# RF-OUT-001.net
KiCad netlist of a schematic drawn in EAGLE
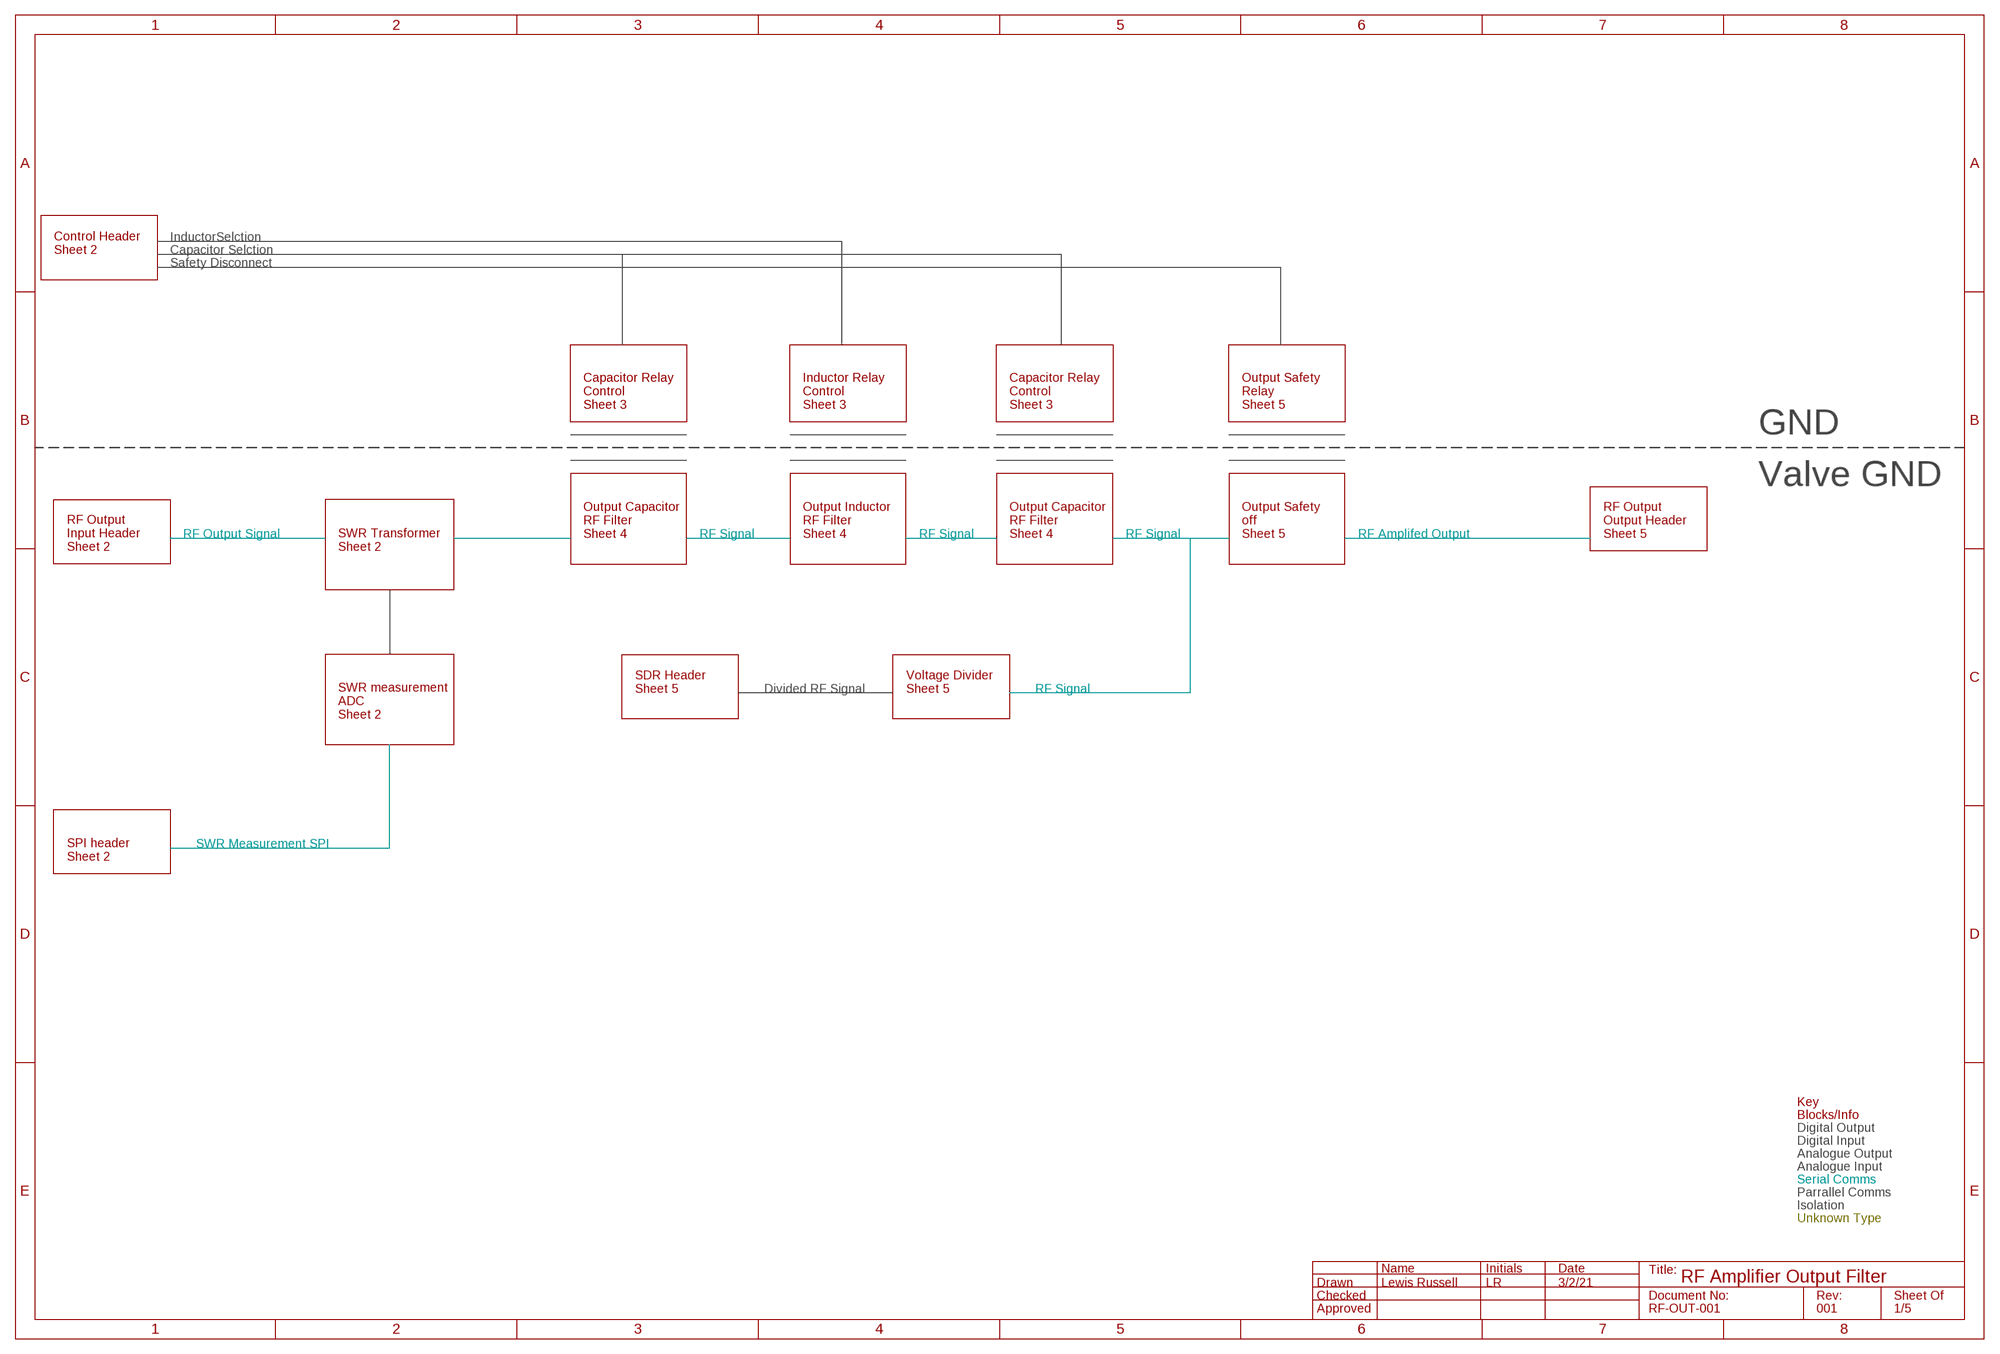
[diagram p0: schematic, sheet 1]
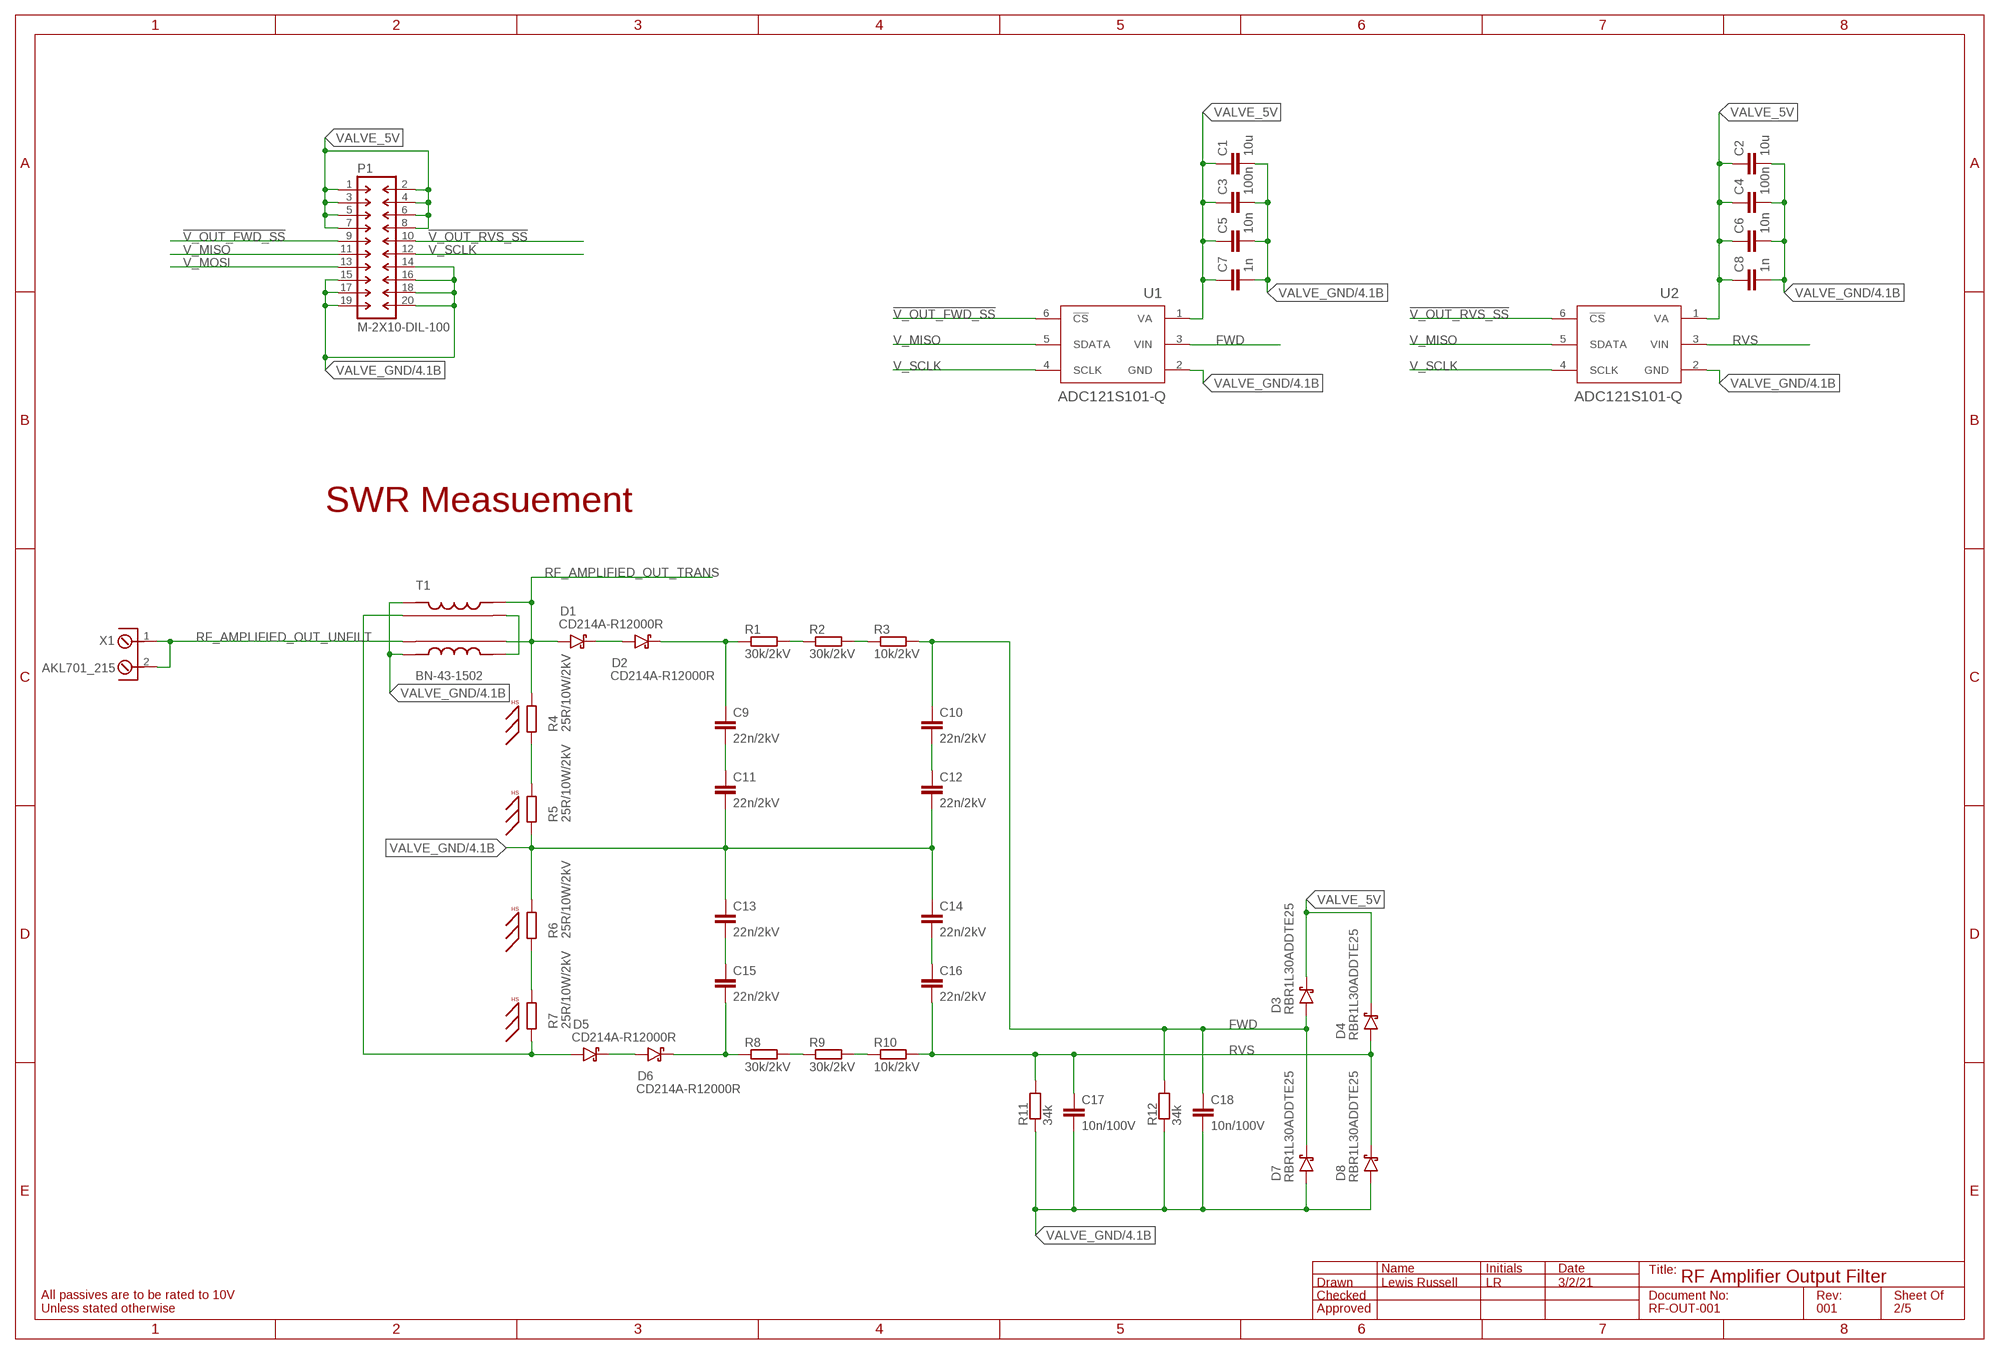
[diagram p1: schematic, sheet 2]
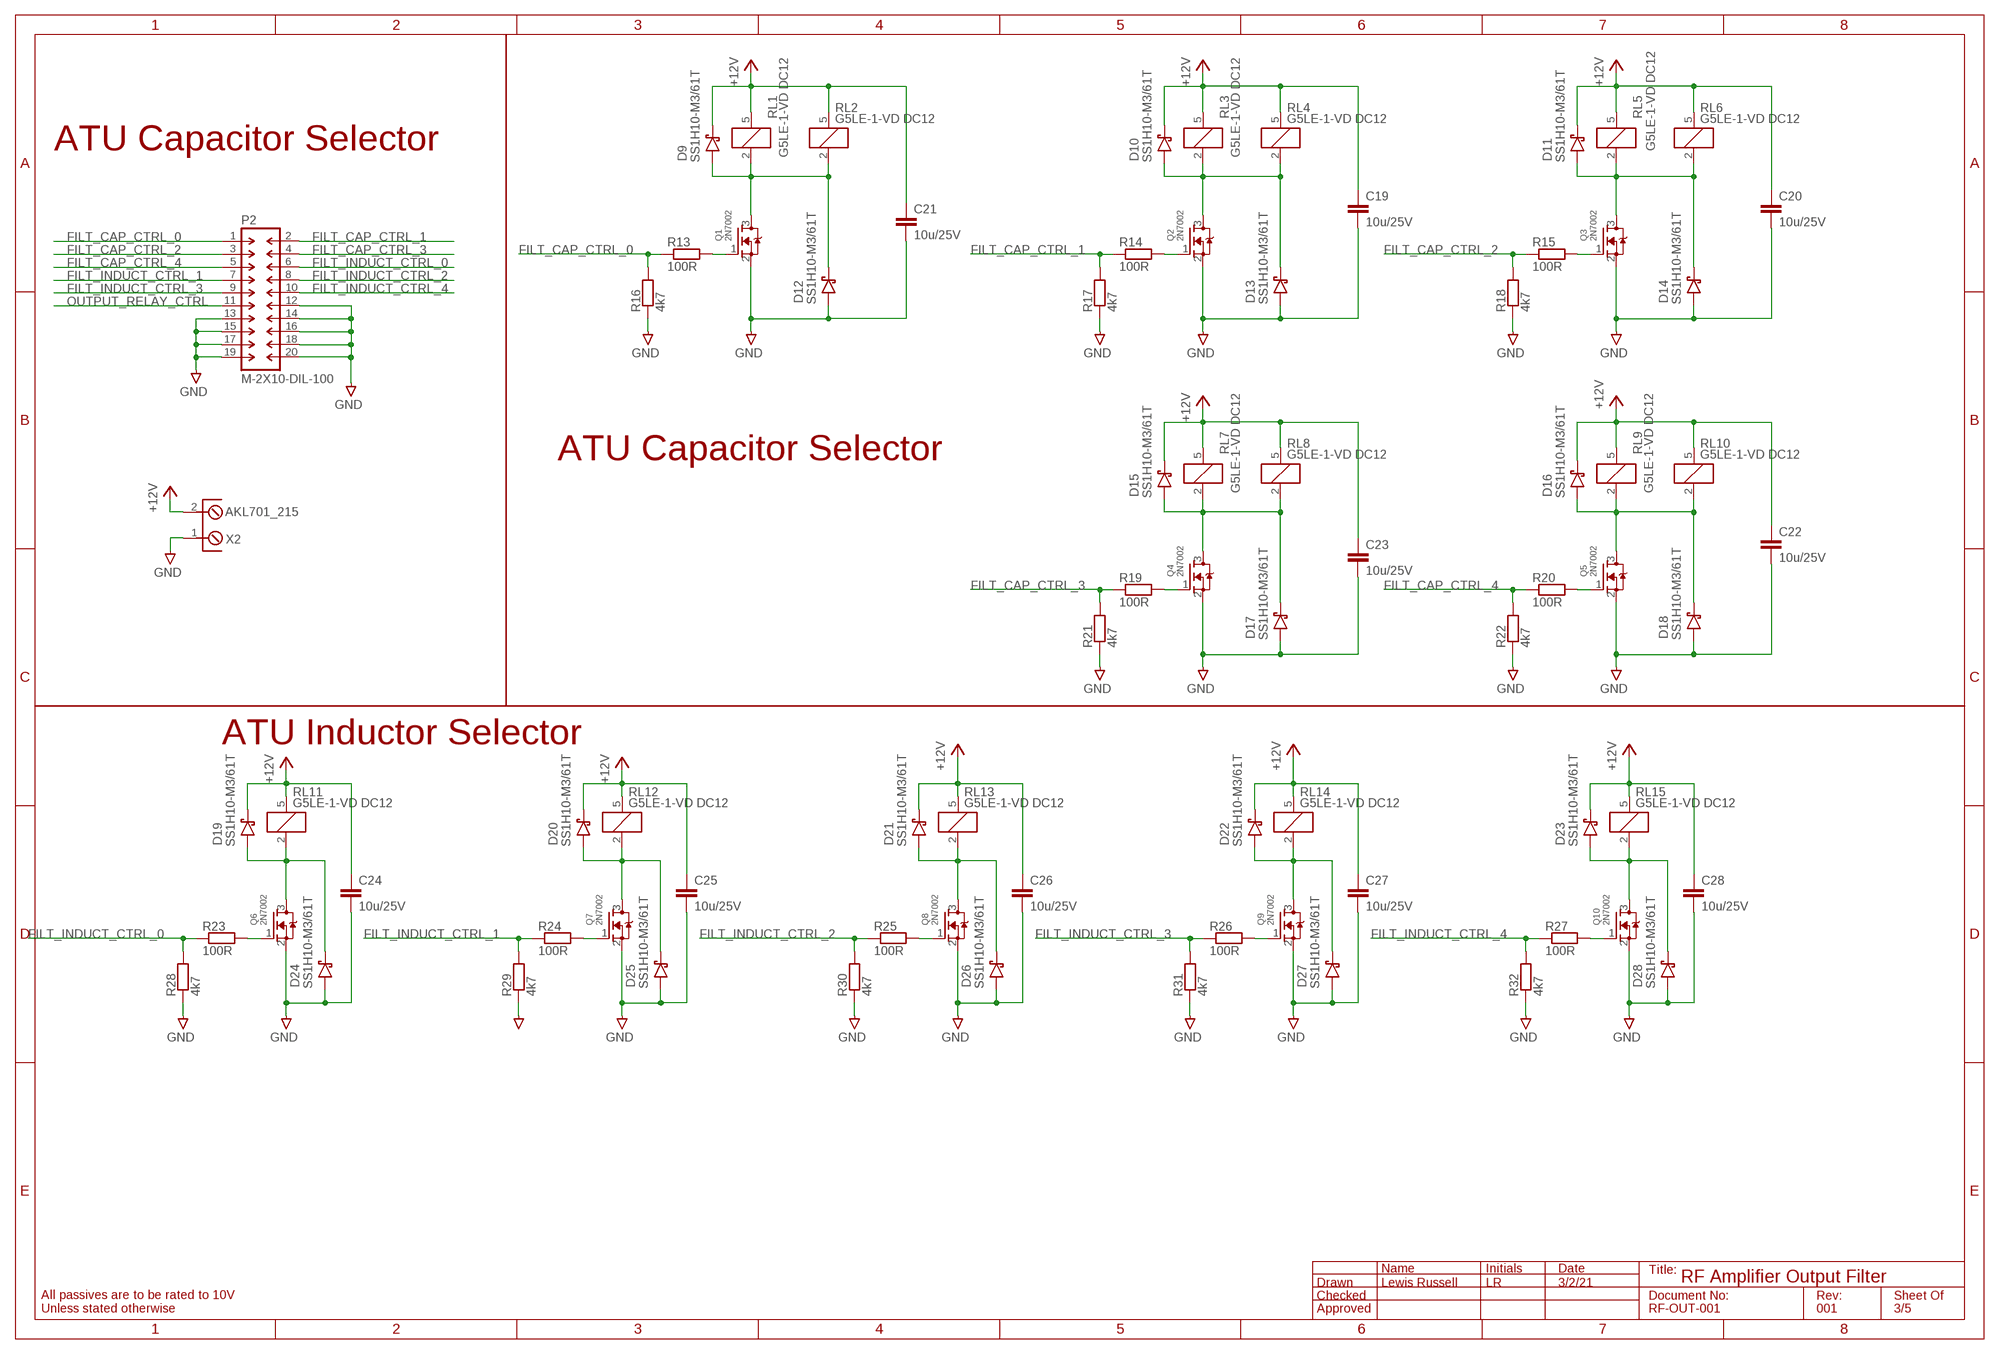
[diagram p2: schematic, sheet 3]
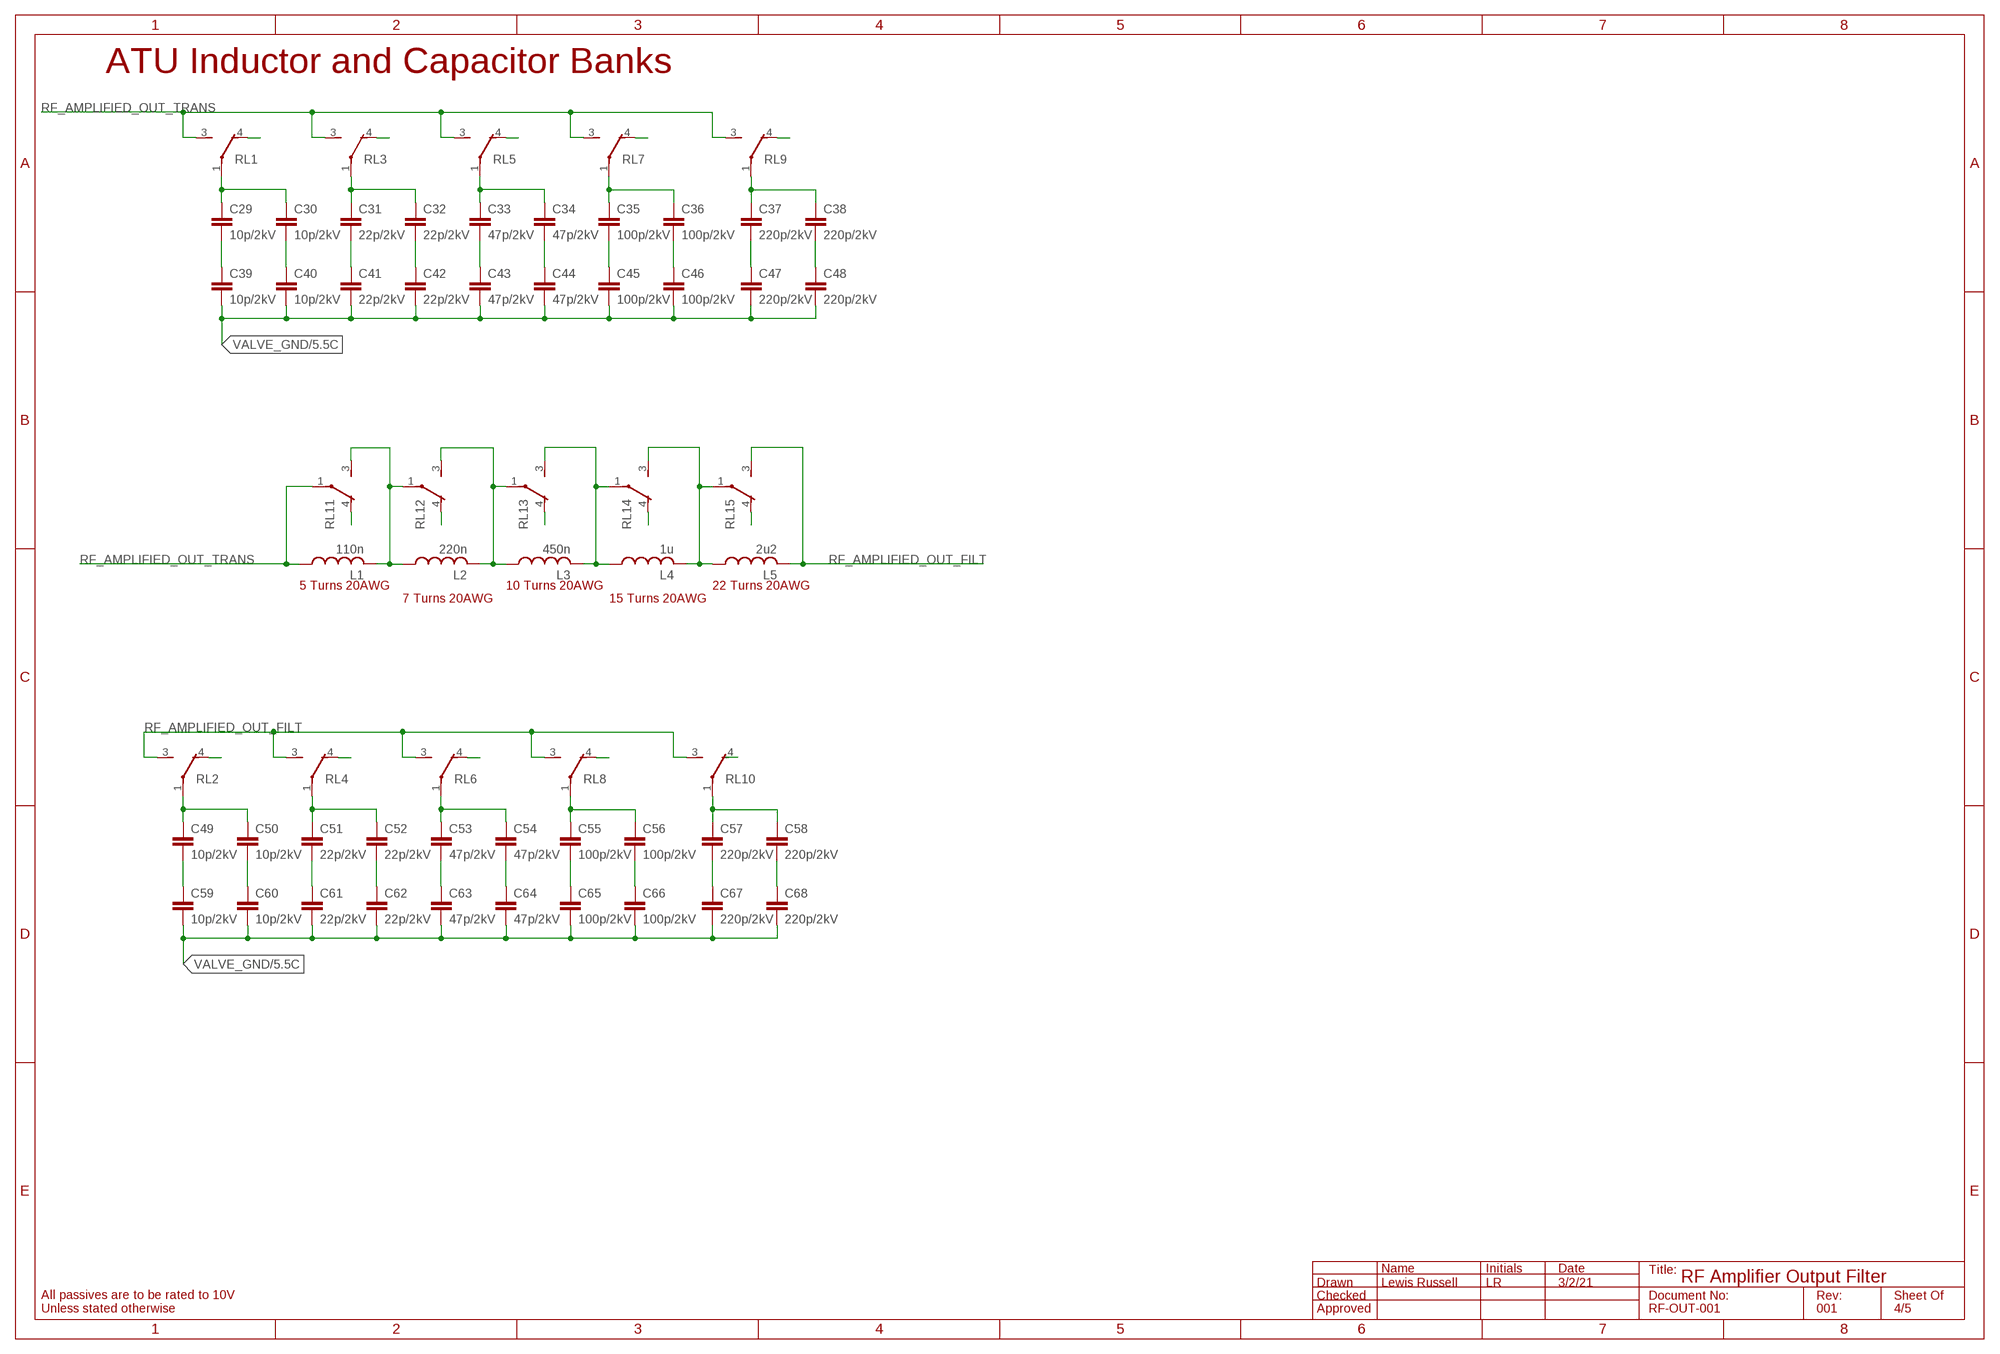
[diagram p3: schematic, sheet 4]
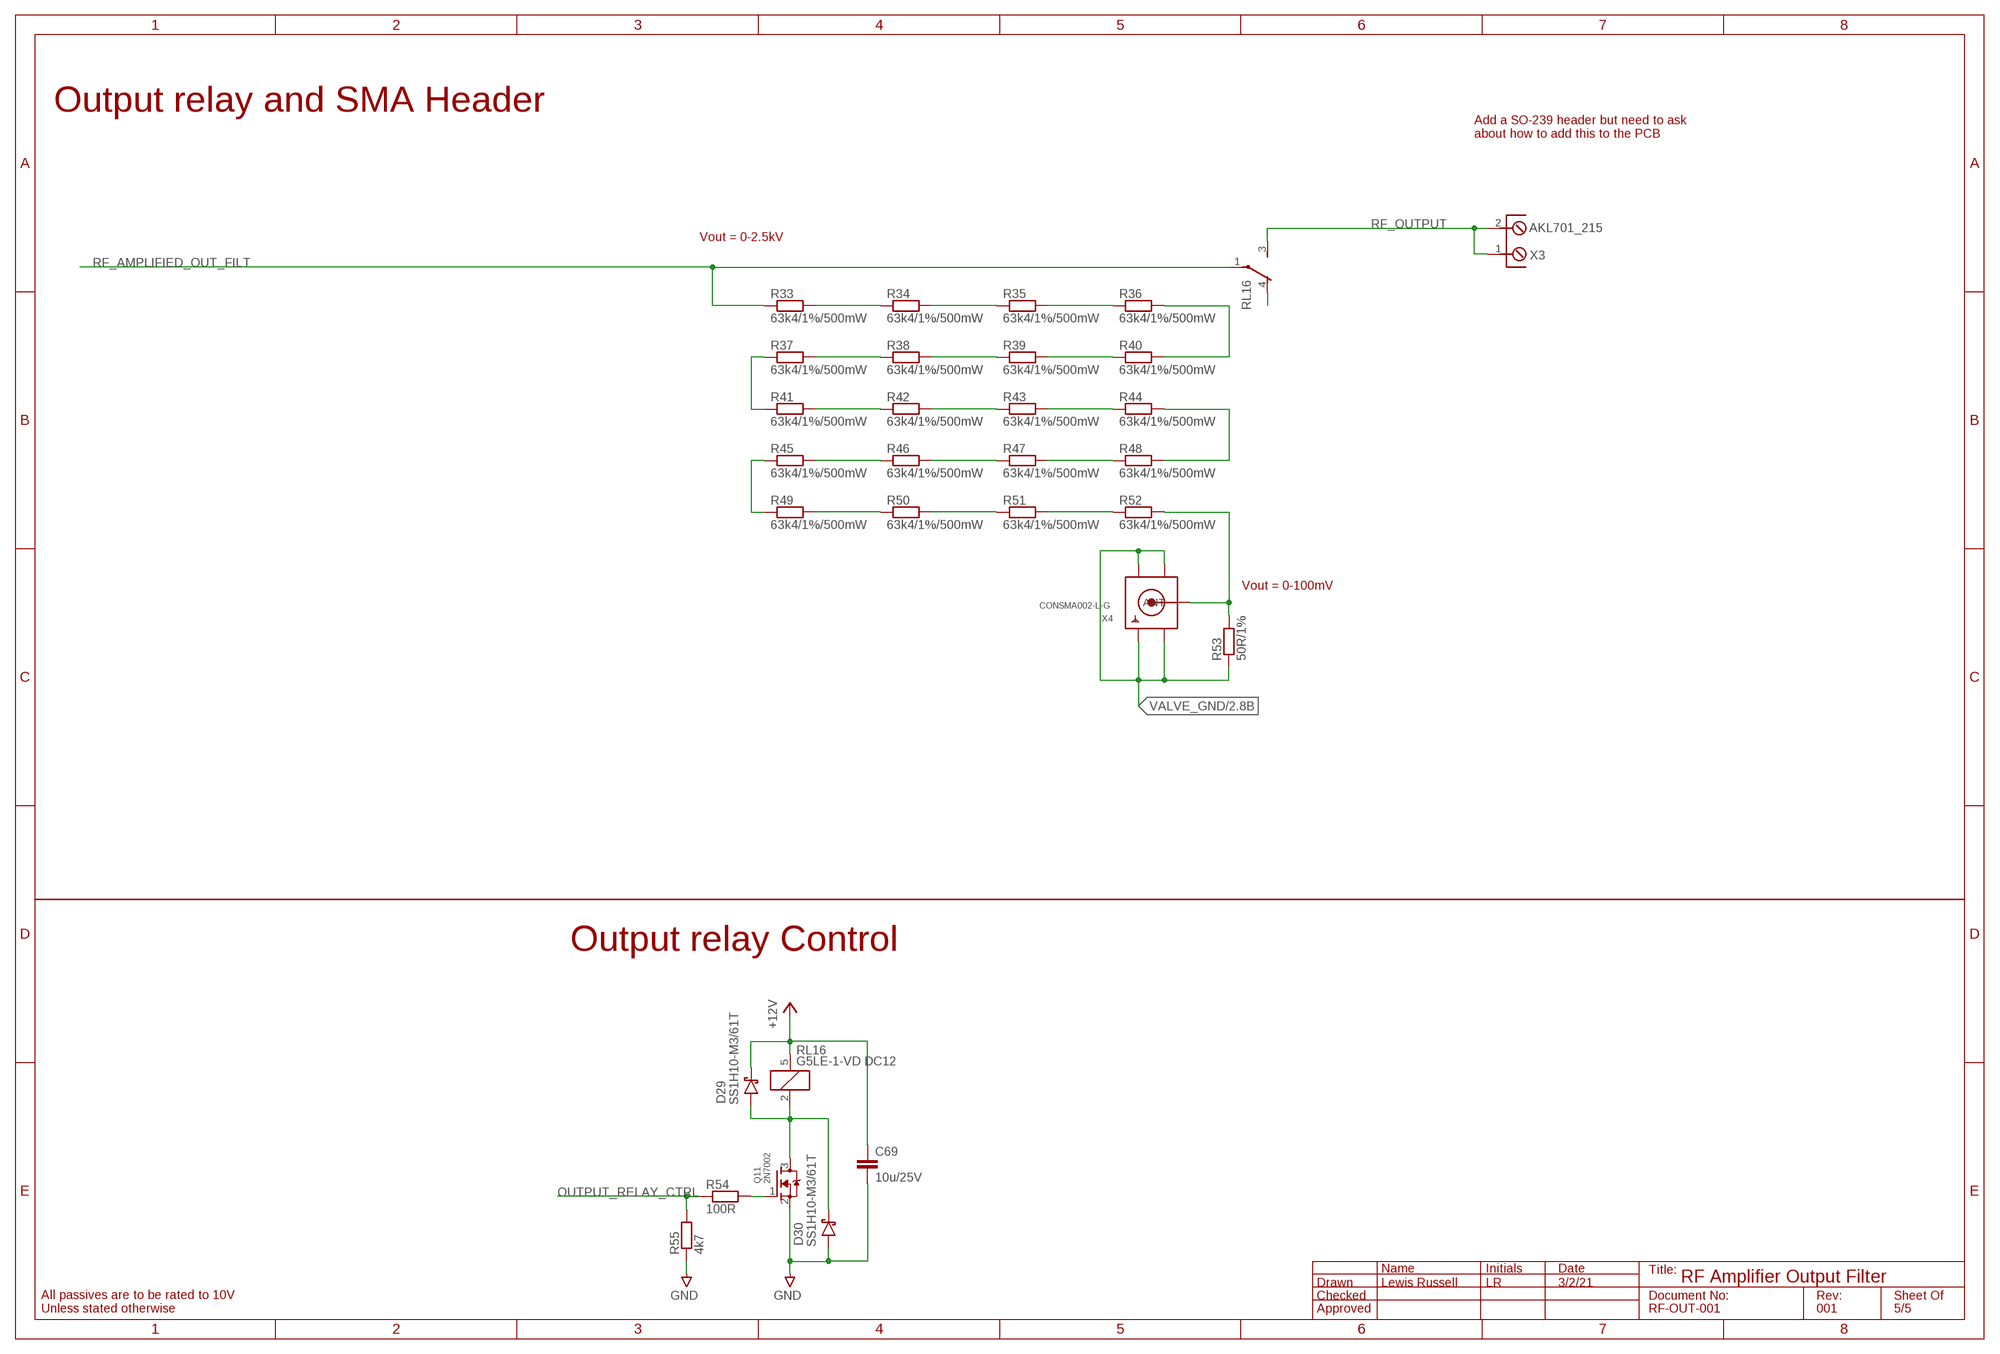
[diagram p4: schematic, sheet 5]

(export (version "E")
  (design (tool "Eeschema 10.0.6"))
  (components
    (comp (ref "C1")
      (value "10u")
      (footprint "eagle-import:C0805")
      (libsource (lib "eagle-import") (part "C-EUC0805"))
    )
    (comp (ref "C2")
      (value "10u")
      (footprint "eagle-import:C0805")
      (libsource (lib "eagle-import") (part "C-EUC0805"))
    )
    (comp (ref "C3")
      (value "100n")
      (footprint "eagle-import:C0603")
      (libsource (lib "eagle-import") (part "C-EUC0603"))
    )
    (comp (ref "C4")
      (value "100n")
      (footprint "eagle-import:C0603")
      (libsource (lib "eagle-import") (part "C-EUC0603"))
    )
    (comp (ref "C5")
      (value "10n")
      (footprint "eagle-import:C0603")
      (libsource (lib "eagle-import") (part "C-EUC0603"))
    )
    (comp (ref "C6")
      (value "10n")
      (footprint "eagle-import:C0603")
      (libsource (lib "eagle-import") (part "C-EUC0603"))
    )
    (comp (ref "C7")
      (value "1n")
      (footprint "eagle-import:C0603")
      (libsource (lib "eagle-import") (part "C-EUC0603"))
    )
    (comp (ref "C8")
      (value "1n")
      (footprint "eagle-import:C0603")
      (libsource (lib "eagle-import") (part "C-EUC0603"))
    )
    (comp (ref "C9")
      (value "22n/2kV")
      (footprint "eagle-import:C2220K")
      (libsource (lib "eagle-import") (part "C-EUC2220K"))
    )
    (comp (ref "C10")
      (value "22n/2kV")
      (footprint "eagle-import:C2220K")
      (libsource (lib "eagle-import") (part "C-EUC2220K"))
    )
    (comp (ref "C11")
      (value "22n/2kV")
      (footprint "eagle-import:C2220K")
      (libsource (lib "eagle-import") (part "C-EUC2220K"))
    )
    (comp (ref "C12")
      (value "22n/2kV")
      (footprint "eagle-import:C2220K")
      (libsource (lib "eagle-import") (part "C-EUC2220K"))
    )
    (comp (ref "C13")
      (value "22n/2kV")
      (footprint "eagle-import:C2220K")
      (libsource (lib "eagle-import") (part "C-EUC2220K"))
    )
    (comp (ref "C14")
      (value "22n/2kV")
      (footprint "eagle-import:C2220K")
      (libsource (lib "eagle-import") (part "C-EUC2220K"))
    )
    (comp (ref "C15")
      (value "22n/2kV")
      (footprint "eagle-import:C2220K")
      (libsource (lib "eagle-import") (part "C-EUC2220K"))
    )
    (comp (ref "C16")
      (value "22n/2kV")
      (footprint "eagle-import:C2220K")
      (libsource (lib "eagle-import") (part "C-EUC2220K"))
    )
    (comp (ref "C17")
      (value "10n/100V")
      (footprint "eagle-import:C0603")
      (libsource (lib "eagle-import") (part "C-EUC0603"))
    )
    (comp (ref "C18")
      (value "10n/100V")
      (footprint "eagle-import:C0603")
      (libsource (lib "eagle-import") (part "C-EUC0603"))
    )
    (comp (ref "D1")
      (value "CD214A-R12000R")
      (footprint "eagle-import:SMB_DO-214AA")
      (libsource (lib "eagle-import") (part "SCHOTTKY_DIODESMB"))
    )
    (comp (ref "D2")
      (value "CD214A-R12000R")
      (footprint "eagle-import:SMB_DO-214AA")
      (libsource (lib "eagle-import") (part "SCHOTTKY_DIODESMB"))
    )
    (comp (ref "D3")
      (value "RBR1L30ADDTE25")
      (footprint "eagle-import:SMA_DO-214AC")
      (libsource (lib "eagle-import") (part "SCHOTTKY_DIODESMA"))
    )
    (comp (ref "D4")
      (value "RBR1L30ADDTE25")
      (footprint "eagle-import:SMA_DO-214AC")
      (libsource (lib "eagle-import") (part "SCHOTTKY_DIODESMA"))
    )
    (comp (ref "D5")
      (value "CD214A-R12000R")
      (footprint "eagle-import:SMB_DO-214AA")
      (libsource (lib "eagle-import") (part "SCHOTTKY_DIODESMB"))
    )
    (comp (ref "D6")
      (value "CD214A-R12000R")
      (footprint "eagle-import:SMB_DO-214AA")
      (libsource (lib "eagle-import") (part "SCHOTTKY_DIODESMB"))
    )
    (comp (ref "D7")
      (value "RBR1L30ADDTE25")
      (footprint "eagle-import:SMA_DO-214AC")
      (libsource (lib "eagle-import") (part "SCHOTTKY_DIODESMA"))
    )
    (comp (ref "D8")
      (value "RBR1L30ADDTE25")
      (footprint "eagle-import:SMA_DO-214AC")
      (libsource (lib "eagle-import") (part "SCHOTTKY_DIODESMA"))
    )
    (comp (ref "P1")
      (value "M-2X10-DIL-100")
      (footprint "eagle-import:DIL-100-2X10")
      (libsource (lib "eagle-import") (part "M-2X10-DIL-100"))
    )
    (comp (ref "R1")
      (value "30k/2kV")
      (footprint "eagle-import:0309_10")
      (libsource (lib "eagle-import") (part "R-EU_0309/10"))
    )
    (comp (ref "R2")
      (value "30k/2kV")
      (footprint "eagle-import:0309_10")
      (libsource (lib "eagle-import") (part "R-EU_0309/10"))
    )
    (comp (ref "R3")
      (value "10k/2kV")
      (footprint "eagle-import:0309_10")
      (libsource (lib "eagle-import") (part "R-EU_0309/10"))
    )
    (comp (ref "R4")
      (value "25R/10W/2kV")
      (footprint "eagle-import:TO220ACS_WITH_WV-T220-101E")
      (libsource (lib "eagle-import") (part "R-EU_W_HS_TO-220-WV-T220-101E"))
    )
    (comp (ref "R5")
      (value "25R/10W/2kV")
      (footprint "eagle-import:TO220ACS_WITH_WV-T220-101E")
      (libsource (lib "eagle-import") (part "R-EU_W_HS_TO-220-WV-T220-101E"))
    )
    (comp (ref "R6")
      (value "25R/10W/2kV")
      (footprint "eagle-import:TO220ACS_WITH_WV-T220-101E")
      (libsource (lib "eagle-import") (part "R-EU_W_HS_TO-220-WV-T220-101E"))
    )
    (comp (ref "R7")
      (value "25R/10W/2kV")
      (footprint "eagle-import:TO220ACS_WITH_WV-T220-101E")
      (libsource (lib "eagle-import") (part "R-EU_W_HS_TO-220-WV-T220-101E"))
    )
    (comp (ref "R8")
      (value "30k/2kV")
      (footprint "eagle-import:0309_10")
      (libsource (lib "eagle-import") (part "R-EU_0309/10"))
    )
    (comp (ref "R9")
      (value "30k/2kV")
      (footprint "eagle-import:0309_10")
      (libsource (lib "eagle-import") (part "R-EU_0309/10"))
    )
    (comp (ref "R10")
      (value "10k/2kV")
      (footprint "eagle-import:0309_10")
      (libsource (lib "eagle-import") (part "R-EU_0309/10"))
    )
    (comp (ref "R11")
      (value "34k")
      (footprint "eagle-import:R0603")
      (libsource (lib "eagle-import") (part "R-EUR0603"))
    )
    (comp (ref "R12")
      (value "34k")
      (footprint "eagle-import:R0603")
      (libsource (lib "eagle-import") (part "R-EUR0603"))
    )
    (comp (ref "T1")
      (value "BN-43-1502")
      (footprint "eagle-import:BN-43-1502")
      (libsource (lib "eagle-import") (part "BN-43-1502"))
    )
    (comp (ref "U1")
      (value "ADC121S101-Q")
      (footprint "eagle-import:SOT23-6")
      (libsource (lib "eagle-import") (part "ADC121S101-Q"))
    )
    (comp (ref "U2")
      (value "ADC121S101-Q")
      (footprint "eagle-import:SOT23-6")
      (libsource (lib "eagle-import") (part "ADC121S101-Q"))
    )
    (comp (ref "X1")
      (value "AKL701_215")
      (footprint "eagle-import:AKL701_2_15")
      (libsource (lib "eagle-import") (part "AKL701_215"))
    )
    (comp (ref "C19")
      (value "10u/25V")
      (footprint "eagle-import:C0805")
      (libsource (lib "eagle-import") (part "C-EUC0805"))
    )
    (comp (ref "C20")
      (value "10u/25V")
      (footprint "eagle-import:C0805")
      (libsource (lib "eagle-import") (part "C-EUC0805"))
    )
    (comp (ref "C21")
      (value "10u/25V")
      (footprint "eagle-import:C0805")
      (libsource (lib "eagle-import") (part "C-EUC0805"))
    )
    (comp (ref "C22")
      (value "10u/25V")
      (footprint "eagle-import:C0805")
      (libsource (lib "eagle-import") (part "C-EUC0805"))
    )
    (comp (ref "C23")
      (value "10u/25V")
      (footprint "eagle-import:C0805")
      (libsource (lib "eagle-import") (part "C-EUC0805"))
    )
    (comp (ref "C24")
      (value "10u/25V")
      (footprint "eagle-import:C0805")
      (libsource (lib "eagle-import") (part "C-EUC0805"))
    )
    (comp (ref "C25")
      (value "10u/25V")
      (footprint "eagle-import:C0805")
      (libsource (lib "eagle-import") (part "C-EUC0805"))
    )
    (comp (ref "C26")
      (value "10u/25V")
      (footprint "eagle-import:C0805")
      (libsource (lib "eagle-import") (part "C-EUC0805"))
    )
    (comp (ref "C27")
      (value "10u/25V")
      (footprint "eagle-import:C0805")
      (libsource (lib "eagle-import") (part "C-EUC0805"))
    )
    (comp (ref "C28")
      (value "10u/25V")
      (footprint "eagle-import:C0805")
      (libsource (lib "eagle-import") (part "C-EUC0805"))
    )
    (comp (ref "D9")
      (value "SS1H10-M3/61T")
      (footprint "eagle-import:SMA_DO-214AC")
      (libsource (lib "eagle-import") (part "SCHOTTKY_DIODESMA"))
    )
    (comp (ref "D10")
      (value "SS1H10-M3/61T")
      (footprint "eagle-import:SMA_DO-214AC")
      (libsource (lib "eagle-import") (part "SCHOTTKY_DIODESMA"))
    )
    (comp (ref "D11")
      (value "SS1H10-M3/61T")
      (footprint "eagle-import:SMA_DO-214AC")
      (libsource (lib "eagle-import") (part "SCHOTTKY_DIODESMA"))
    )
    (comp (ref "D12")
      (value "SS1H10-M3/61T")
      (footprint "eagle-import:SMA_DO-214AC")
      (libsource (lib "eagle-import") (part "SCHOTTKY_DIODESMA"))
    )
    (comp (ref "D13")
      (value "SS1H10-M3/61T")
      (footprint "eagle-import:SMA_DO-214AC")
      (libsource (lib "eagle-import") (part "SCHOTTKY_DIODESMA"))
    )
    (comp (ref "D14")
      (value "SS1H10-M3/61T")
      (footprint "eagle-import:SMA_DO-214AC")
      (libsource (lib "eagle-import") (part "SCHOTTKY_DIODESMA"))
    )
    (comp (ref "D15")
      (value "SS1H10-M3/61T")
      (footprint "eagle-import:SMA_DO-214AC")
      (libsource (lib "eagle-import") (part "SCHOTTKY_DIODESMA"))
    )
    (comp (ref "D16")
      (value "SS1H10-M3/61T")
      (footprint "eagle-import:SMA_DO-214AC")
      (libsource (lib "eagle-import") (part "SCHOTTKY_DIODESMA"))
    )
    (comp (ref "D17")
      (value "SS1H10-M3/61T")
      (footprint "eagle-import:SMA_DO-214AC")
      (libsource (lib "eagle-import") (part "SCHOTTKY_DIODESMA"))
    )
    (comp (ref "D18")
      (value "SS1H10-M3/61T")
      (footprint "eagle-import:SMA_DO-214AC")
      (libsource (lib "eagle-import") (part "SCHOTTKY_DIODESMA"))
    )
    (comp (ref "D19")
      (value "SS1H10-M3/61T")
      (footprint "eagle-import:SMA_DO-214AC")
      (libsource (lib "eagle-import") (part "SCHOTTKY_DIODESMA"))
    )
    (comp (ref "D20")
      (value "SS1H10-M3/61T")
      (footprint "eagle-import:SMA_DO-214AC")
      (libsource (lib "eagle-import") (part "SCHOTTKY_DIODESMA"))
    )
    (comp (ref "D21")
      (value "SS1H10-M3/61T")
      (footprint "eagle-import:SMA_DO-214AC")
      (libsource (lib "eagle-import") (part "SCHOTTKY_DIODESMA"))
    )
    (comp (ref "D22")
      (value "SS1H10-M3/61T")
      (footprint "eagle-import:SMA_DO-214AC")
      (libsource (lib "eagle-import") (part "SCHOTTKY_DIODESMA"))
    )
    (comp (ref "D23")
      (value "SS1H10-M3/61T")
      (footprint "eagle-import:SMA_DO-214AC")
      (libsource (lib "eagle-import") (part "SCHOTTKY_DIODESMA"))
    )
    (comp (ref "D24")
      (value "SS1H10-M3/61T")
      (footprint "eagle-import:SMA_DO-214AC")
      (libsource (lib "eagle-import") (part "SCHOTTKY_DIODESMA"))
    )
    (comp (ref "D25")
      (value "SS1H10-M3/61T")
      (footprint "eagle-import:SMA_DO-214AC")
      (libsource (lib "eagle-import") (part "SCHOTTKY_DIODESMA"))
    )
    (comp (ref "D26")
      (value "SS1H10-M3/61T")
      (footprint "eagle-import:SMA_DO-214AC")
      (libsource (lib "eagle-import") (part "SCHOTTKY_DIODESMA"))
    )
    (comp (ref "D27")
      (value "SS1H10-M3/61T")
      (footprint "eagle-import:SMA_DO-214AC")
      (libsource (lib "eagle-import") (part "SCHOTTKY_DIODESMA"))
    )
    (comp (ref "D28")
      (value "SS1H10-M3/61T")
      (footprint "eagle-import:SMA_DO-214AC")
      (libsource (lib "eagle-import") (part "SCHOTTKY_DIODESMA"))
    )
    (comp (ref "P2")
      (value "M-2X10-DIL-100")
      (footprint "eagle-import:DIL-100-2X10")
      (libsource (lib "eagle-import") (part "M-2X10-DIL-100"))
    )
    (comp (ref "Q1")
      (value "2N7002")
      (footprint "eagle-import:SOT23")
      (libsource (lib "eagle-import") (part "MOSFET-NREFLOW"))
    )
    (comp (ref "Q2")
      (value "2N7002")
      (footprint "eagle-import:SOT23")
      (libsource (lib "eagle-import") (part "MOSFET-NREFLOW"))
    )
    (comp (ref "Q3")
      (value "2N7002")
      (footprint "eagle-import:SOT23")
      (libsource (lib "eagle-import") (part "MOSFET-NREFLOW"))
    )
    (comp (ref "Q4")
      (value "2N7002")
      (footprint "eagle-import:SOT23")
      (libsource (lib "eagle-import") (part "MOSFET-NREFLOW"))
    )
    (comp (ref "Q5")
      (value "2N7002")
      (footprint "eagle-import:SOT23")
      (libsource (lib "eagle-import") (part "MOSFET-NREFLOW"))
    )
    (comp (ref "Q6")
      (value "2N7002")
      (footprint "eagle-import:SOT23")
      (libsource (lib "eagle-import") (part "MOSFET-NREFLOW"))
    )
    (comp (ref "Q7")
      (value "2N7002")
      (footprint "eagle-import:SOT23")
      (libsource (lib "eagle-import") (part "MOSFET-NREFLOW"))
    )
    (comp (ref "Q8")
      (value "2N7002")
      (footprint "eagle-import:SOT23")
      (libsource (lib "eagle-import") (part "MOSFET-NREFLOW"))
    )
    (comp (ref "Q9")
      (value "2N7002")
      (footprint "eagle-import:SOT23")
      (libsource (lib "eagle-import") (part "MOSFET-NREFLOW"))
    )
    (comp (ref "Q10")
      (value "2N7002")
      (footprint "eagle-import:SOT23")
      (libsource (lib "eagle-import") (part "MOSFET-NREFLOW"))
    )
    (comp (ref "R13")
      (value "100R")
      (footprint "eagle-import:R0603")
      (libsource (lib "eagle-import") (part "R-EUR0603"))
    )
    (comp (ref "R14")
      (value "100R")
      (footprint "eagle-import:R0603")
      (libsource (lib "eagle-import") (part "R-EUR0603"))
    )
    (comp (ref "R15")
      (value "100R")
      (footprint "eagle-import:R0603")
      (libsource (lib "eagle-import") (part "R-EUR0603"))
    )
    (comp (ref "R16")
      (value "4k7")
      (footprint "eagle-import:R0603")
      (libsource (lib "eagle-import") (part "R-EUR0603"))
    )
    (comp (ref "R17")
      (value "4k7")
      (footprint "eagle-import:R0603")
      (libsource (lib "eagle-import") (part "R-EUR0603"))
    )
    (comp (ref "R18")
      (value "4k7")
      (footprint "eagle-import:R0603")
      (libsource (lib "eagle-import") (part "R-EUR0603"))
    )
    (comp (ref "R19")
      (value "100R")
      (footprint "eagle-import:R0603")
      (libsource (lib "eagle-import") (part "R-EUR0603"))
    )
    (comp (ref "R20")
      (value "100R")
      (footprint "eagle-import:R0603")
      (libsource (lib "eagle-import") (part "R-EUR0603"))
    )
    (comp (ref "R21")
      (value "4k7")
      (footprint "eagle-import:R0603")
      (libsource (lib "eagle-import") (part "R-EUR0603"))
    )
    (comp (ref "R22")
      (value "4k7")
      (footprint "eagle-import:R0603")
      (libsource (lib "eagle-import") (part "R-EUR0603"))
    )
    (comp (ref "R23")
      (value "100R")
      (footprint "eagle-import:R0603")
      (libsource (lib "eagle-import") (part "R-EUR0603"))
    )
    (comp (ref "R24")
      (value "100R")
      (footprint "eagle-import:R0603")
      (libsource (lib "eagle-import") (part "R-EUR0603"))
    )
    (comp (ref "R25")
      (value "100R")
      (footprint "eagle-import:R0603")
      (libsource (lib "eagle-import") (part "R-EUR0603"))
    )
    (comp (ref "R26")
      (value "100R")
      (footprint "eagle-import:R0603")
      (libsource (lib "eagle-import") (part "R-EUR0603"))
    )
    (comp (ref "R27")
      (value "100R")
      (footprint "eagle-import:R0603")
      (libsource (lib "eagle-import") (part "R-EUR0603"))
    )
    (comp (ref "R28")
      (value "4k7")
      (footprint "eagle-import:R0603")
      (libsource (lib "eagle-import") (part "R-EUR0603"))
    )
    (comp (ref "R29")
      (value "4k7")
      (footprint "eagle-import:R0603")
      (libsource (lib "eagle-import") (part "R-EUR0603"))
    )
    (comp (ref "R30")
      (value "4k7")
      (footprint "eagle-import:R0603")
      (libsource (lib "eagle-import") (part "R-EUR0603"))
    )
    (comp (ref "R31")
      (value "4k7")
      (footprint "eagle-import:R0603")
      (libsource (lib "eagle-import") (part "R-EUR0603"))
    )
    (comp (ref "R32")
      (value "4k7")
      (footprint "eagle-import:R0603")
      (libsource (lib "eagle-import") (part "R-EUR0603"))
    )
    (comp (ref "RL1")
      (value "G5LE-1-VD DC12")
      (footprint "eagle-import:SPDT")
      (libsource (lib "eagle-import") (part "G5LE-E"))
    )
    (comp (ref "RL2")
      (value "G5LE-1-VD DC12")
      (footprint "eagle-import:SPDT")
      (libsource (lib "eagle-import") (part "G5LE-E"))
    )
    (comp (ref "RL3")
      (value "G5LE-1-VD DC12")
      (footprint "eagle-import:SPDT")
      (libsource (lib "eagle-import") (part "G5LE-E"))
    )
    (comp (ref "RL4")
      (value "G5LE-1-VD DC12")
      (footprint "eagle-import:SPDT")
      (libsource (lib "eagle-import") (part "G5LE-E"))
    )
    (comp (ref "RL5")
      (value "G5LE-1-VD DC12")
      (footprint "eagle-import:SPDT")
      (libsource (lib "eagle-import") (part "G5LE-E"))
    )
    (comp (ref "RL6")
      (value "G5LE-1-VD DC12")
      (footprint "eagle-import:SPDT")
      (libsource (lib "eagle-import") (part "G5LE-E"))
    )
    (comp (ref "RL7")
      (value "G5LE-1-VD DC12")
      (footprint "eagle-import:SPDT")
      (libsource (lib "eagle-import") (part "G5LE-E"))
    )
    (comp (ref "RL8")
      (value "G5LE-1-VD DC12")
      (footprint "eagle-import:SPDT")
      (libsource (lib "eagle-import") (part "G5LE-E"))
    )
    (comp (ref "RL9")
      (value "G5LE-1-VD DC12")
      (footprint "eagle-import:SPDT")
      (libsource (lib "eagle-import") (part "G5LE-E"))
    )
    (comp (ref "RL10")
      (value "G5LE-1-VD DC12")
      (footprint "eagle-import:SPDT")
      (libsource (lib "eagle-import") (part "G5LE-E"))
    )
    (comp (ref "RL11")
      (value "G5LE-1-VD DC12")
      (footprint "eagle-import:SPDT")
      (libsource (lib "eagle-import") (part "G5LE-E"))
    )
    (comp (ref "RL12")
      (value "G5LE-1-VD DC12")
      (footprint "eagle-import:SPDT")
      (libsource (lib "eagle-import") (part "G5LE-E"))
    )
    (comp (ref "RL13")
      (value "G5LE-1-VD DC12")
      (footprint "eagle-import:SPDT")
      (libsource (lib "eagle-import") (part "G5LE-E"))
    )
    (comp (ref "RL14")
      (value "G5LE-1-VD DC12")
      (footprint "eagle-import:SPDT")
      (libsource (lib "eagle-import") (part "G5LE-E"))
    )
    (comp (ref "RL15")
      (value "G5LE-1-VD DC12")
      (footprint "eagle-import:SPDT")
      (libsource (lib "eagle-import") (part "G5LE-E"))
    )
    (comp (ref "X2")
      (value "AKL701_215")
      (footprint "eagle-import:AKL701_2_15")
      (libsource (lib "eagle-import") (part "AKL701_215"))
    )
    (comp (ref "C29")
      (value "10p/2kV")
      (footprint "eagle-import:C050-055X075")
      (libsource (lib "eagle-import") (part "rcl_334_C-EU050-055X075"))
    )
    (comp (ref "C30")
      (value "10p/2kV")
      (footprint "eagle-import:C050-055X075")
      (libsource (lib "eagle-import") (part "rcl_334_C-EU050-055X075"))
    )
    (comp (ref "C31")
      (value "22p/2kV")
      (footprint "eagle-import:C050-055X075")
      (libsource (lib "eagle-import") (part "rcl_334_C-EU050-055X075"))
    )
    (comp (ref "C32")
      (value "22p/2kV")
      (footprint "eagle-import:C050-055X075")
      (libsource (lib "eagle-import") (part "rcl_334_C-EU050-055X075"))
    )
    (comp (ref "C33")
      (value "47p/2kV")
      (footprint "eagle-import:C050-055X075")
      (libsource (lib "eagle-import") (part "rcl_334_C-EU050-055X075"))
    )
    (comp (ref "C34")
      (value "47p/2kV")
      (footprint "eagle-import:C050-055X075")
      (libsource (lib "eagle-import") (part "rcl_334_C-EU050-055X075"))
    )
    (comp (ref "C35")
      (value "100p/2kV")
      (footprint "eagle-import:C050-075X075")
      (libsource (lib "eagle-import") (part "rcl_334_C-EU050-075X075"))
    )
    (comp (ref "C36")
      (value "100p/2kV")
      (footprint "eagle-import:C050-075X075")
      (libsource (lib "eagle-import") (part "rcl_334_C-EU050-075X075"))
    )
    (comp (ref "C37")
      (value "220p/2kV")
      (footprint "eagle-import:C050-075X075")
      (libsource (lib "eagle-import") (part "rcl_334_C-EU050-075X075"))
    )
    (comp (ref "C38")
      (value "220p/2kV")
      (footprint "eagle-import:C050-075X075")
      (libsource (lib "eagle-import") (part "rcl_334_C-EU050-075X075"))
    )
    (comp (ref "C39")
      (value "10p/2kV")
      (footprint "eagle-import:C050-055X075")
      (libsource (lib "eagle-import") (part "rcl_334_C-EU050-055X075"))
    )
    (comp (ref "C40")
      (value "10p/2kV")
      (footprint "eagle-import:C050-055X075")
      (libsource (lib "eagle-import") (part "rcl_334_C-EU050-055X075"))
    )
    (comp (ref "C41")
      (value "22p/2kV")
      (footprint "eagle-import:C050-055X075")
      (libsource (lib "eagle-import") (part "rcl_334_C-EU050-055X075"))
    )
    (comp (ref "C42")
      (value "22p/2kV")
      (footprint "eagle-import:C050-055X075")
      (libsource (lib "eagle-import") (part "rcl_334_C-EU050-055X075"))
    )
    (comp (ref "C43")
      (value "47p/2kV")
      (footprint "eagle-import:C050-055X075")
      (libsource (lib "eagle-import") (part "rcl_334_C-EU050-055X075"))
    )
    (comp (ref "C44")
      (value "47p/2kV")
      (footprint "eagle-import:C050-055X075")
      (libsource (lib "eagle-import") (part "rcl_334_C-EU050-055X075"))
    )
    (comp (ref "C45")
      (value "100p/2kV")
      (footprint "eagle-import:C050-075X075")
      (libsource (lib "eagle-import") (part "rcl_334_C-EU050-075X075"))
    )
    (comp (ref "C46")
      (value "100p/2kV")
      (footprint "eagle-import:C050-075X075")
      (libsource (lib "eagle-import") (part "rcl_334_C-EU050-075X075"))
    )
    (comp (ref "C47")
      (value "220p/2kV")
      (footprint "eagle-import:C050-075X075")
      (libsource (lib "eagle-import") (part "rcl_334_C-EU050-075X075"))
    )
    (comp (ref "C48")
      (value "220p/2kV")
      (footprint "eagle-import:C050-075X075")
      (libsource (lib "eagle-import") (part "rcl_334_C-EU050-075X075"))
    )
    (comp (ref "C49")
      (value "10p/2kV")
      (footprint "eagle-import:C050-055X075")
      (libsource (lib "eagle-import") (part "rcl_334_C-EU050-055X075"))
    )
    (comp (ref "C50")
      (value "10p/2kV")
      (footprint "eagle-import:C050-055X075")
      (libsource (lib "eagle-import") (part "rcl_334_C-EU050-055X075"))
    )
    (comp (ref "C51")
      (value "22p/2kV")
      (footprint "eagle-import:C050-055X075")
      (libsource (lib "eagle-import") (part "rcl_334_C-EU050-055X075"))
    )
    (comp (ref "C52")
      (value "22p/2kV")
      (footprint "eagle-import:C050-055X075")
      (libsource (lib "eagle-import") (part "rcl_334_C-EU050-055X075"))
    )
    (comp (ref "C53")
      (value "47p/2kV")
      (footprint "eagle-import:C050-055X075")
      (libsource (lib "eagle-import") (part "rcl_334_C-EU050-055X075"))
    )
    (comp (ref "C54")
      (value "47p/2kV")
      (footprint "eagle-import:C050-055X075")
      (libsource (lib "eagle-import") (part "rcl_334_C-EU050-055X075"))
    )
    (comp (ref "C55")
      (value "100p/2kV")
      (footprint "eagle-import:C050-075X075")
      (libsource (lib "eagle-import") (part "rcl_334_C-EU050-075X075"))
    )
    (comp (ref "C56")
      (value "100p/2kV")
      (footprint "eagle-import:C050-075X075")
      (libsource (lib "eagle-import") (part "rcl_334_C-EU050-075X075"))
    )
    (comp (ref "C57")
      (value "220p/2kV")
      (footprint "eagle-import:C050-075X075")
      (libsource (lib "eagle-import") (part "rcl_334_C-EU050-075X075"))
    )
    (comp (ref "C58")
      (value "220p/2kV")
      (footprint "eagle-import:C050-075X075")
      (libsource (lib "eagle-import") (part "rcl_334_C-EU050-075X075"))
    )
    (comp (ref "C59")
      (value "10p/2kV")
      (footprint "eagle-import:C050-055X075")
      (libsource (lib "eagle-import") (part "rcl_334_C-EU050-055X075"))
    )
    (comp (ref "C60")
      (value "10p/2kV")
      (footprint "eagle-import:C050-055X075")
      (libsource (lib "eagle-import") (part "rcl_334_C-EU050-055X075"))
    )
    (comp (ref "C61")
      (value "22p/2kV")
      (footprint "eagle-import:C050-055X075")
      (libsource (lib "eagle-import") (part "rcl_334_C-EU050-055X075"))
    )
    (comp (ref "C62")
      (value "22p/2kV")
      (footprint "eagle-import:C050-055X075")
      (libsource (lib "eagle-import") (part "rcl_334_C-EU050-055X075"))
    )
    (comp (ref "C63")
      (value "47p/2kV")
      (footprint "eagle-import:C050-055X075")
      (libsource (lib "eagle-import") (part "rcl_334_C-EU050-055X075"))
    )
    (comp (ref "C64")
      (value "47p/2kV")
      (footprint "eagle-import:C050-055X075")
      (libsource (lib "eagle-import") (part "rcl_334_C-EU050-055X075"))
    )
    (comp (ref "C65")
      (value "100p/2kV")
      (footprint "eagle-import:C050-075X075")
      (libsource (lib "eagle-import") (part "rcl_334_C-EU050-075X075"))
    )
    (comp (ref "C66")
      (value "100p/2kV")
      (footprint "eagle-import:C050-075X075")
      (libsource (lib "eagle-import") (part "rcl_334_C-EU050-075X075"))
    )
    (comp (ref "C67")
      (value "220p/2kV")
      (footprint "eagle-import:C050-075X075")
      (libsource (lib "eagle-import") (part "rcl_334_C-EU050-075X075"))
    )
    (comp (ref "C68")
      (value "220p/2kV")
      (footprint "eagle-import:C050-075X075")
      (libsource (lib "eagle-import") (part "rcl_334_C-EU050-075X075"))
    )
    (comp (ref "L1")
      (value "110n")
      (footprint "eagle-import:T80-6")
      (libsource (lib "eagle-import") (part "T80-6"))
    )
    (comp (ref "L2")
      (value "220n")
      (footprint "eagle-import:T80-6")
      (libsource (lib "eagle-import") (part "T80-6"))
    )
    (comp (ref "L3")
      (value "450n")
      (footprint "eagle-import:T80-6")
      (libsource (lib "eagle-import") (part "T80-6"))
    )
    (comp (ref "L4")
      (value "1u")
      (footprint "eagle-import:T80-6")
      (libsource (lib "eagle-import") (part "T80-6"))
    )
    (comp (ref "L5")
      (value "2u2")
      (footprint "eagle-import:T80-6")
      (libsource (lib "eagle-import") (part "T80-6"))
    )
    (comp (ref "C69")
      (value "10u/25V")
      (footprint "eagle-import:C0805")
      (libsource (lib "eagle-import") (part "C-EUC0805"))
    )
    (comp (ref "D29")
      (value "SS1H10-M3/61T")
      (footprint "eagle-import:SMA_DO-214AC")
      (libsource (lib "eagle-import") (part "SCHOTTKY_DIODESMA"))
    )
    (comp (ref "D30")
      (value "SS1H10-M3/61T")
      (footprint "eagle-import:SMA_DO-214AC")
      (libsource (lib "eagle-import") (part "SCHOTTKY_DIODESMA"))
    )
    (comp (ref "Q11")
      (value "2N7002")
      (footprint "eagle-import:SOT23")
      (libsource (lib "eagle-import") (part "MOSFET-NREFLOW"))
    )
    (comp (ref "R33")
      (value "63k4/1%/500mW")
      (footprint "eagle-import:R0805")
      (libsource (lib "eagle-import") (part "R-EUR0805"))
    )
    (comp (ref "R34")
      (value "63k4/1%/500mW")
      (footprint "eagle-import:R0805")
      (libsource (lib "eagle-import") (part "R-EUR0805"))
    )
    (comp (ref "R35")
      (value "63k4/1%/500mW")
      (footprint "eagle-import:R0805")
      (libsource (lib "eagle-import") (part "R-EUR0805"))
    )
    (comp (ref "R36")
      (value "63k4/1%/500mW")
      (footprint "eagle-import:R0805")
      (libsource (lib "eagle-import") (part "R-EUR0805"))
    )
    (comp (ref "R37")
      (value "63k4/1%/500mW")
      (footprint "eagle-import:R0805")
      (libsource (lib "eagle-import") (part "R-EUR0805"))
    )
    (comp (ref "R38")
      (value "63k4/1%/500mW")
      (footprint "eagle-import:R0805")
      (libsource (lib "eagle-import") (part "R-EUR0805"))
    )
    (comp (ref "R39")
      (value "63k4/1%/500mW")
      (footprint "eagle-import:R0805")
      (libsource (lib "eagle-import") (part "R-EUR0805"))
    )
    (comp (ref "R40")
      (value "63k4/1%/500mW")
      (footprint "eagle-import:R0805")
      (libsource (lib "eagle-import") (part "R-EUR0805"))
    )
    (comp (ref "R41")
      (value "63k4/1%/500mW")
      (footprint "eagle-import:R0805")
      (libsource (lib "eagle-import") (part "R-EUR0805"))
    )
    (comp (ref "R42")
      (value "63k4/1%/500mW")
      (footprint "eagle-import:R0805")
      (libsource (lib "eagle-import") (part "R-EUR0805"))
    )
    (comp (ref "R43")
      (value "63k4/1%/500mW")
      (footprint "eagle-import:R0805")
      (libsource (lib "eagle-import") (part "R-EUR0805"))
    )
    (comp (ref "R44")
      (value "63k4/1%/500mW")
      (footprint "eagle-import:R0805")
      (libsource (lib "eagle-import") (part "R-EUR0805"))
    )
    (comp (ref "R45")
      (value "63k4/1%/500mW")
      (footprint "eagle-import:R0805")
      (libsource (lib "eagle-import") (part "R-EUR0805"))
    )
    (comp (ref "R46")
      (value "63k4/1%/500mW")
      (footprint "eagle-import:R0805")
      (libsource (lib "eagle-import") (part "R-EUR0805"))
    )
    (comp (ref "R47")
      (value "63k4/1%/500mW")
      (footprint "eagle-import:R0805")
      (libsource (lib "eagle-import") (part "R-EUR0805"))
    )
    (comp (ref "R48")
      (value "63k4/1%/500mW")
      (footprint "eagle-import:R0805")
      (libsource (lib "eagle-import") (part "R-EUR0805"))
    )
    (comp (ref "R49")
      (value "63k4/1%/500mW")
      (footprint "eagle-import:R0805")
      (libsource (lib "eagle-import") (part "R-EUR0805"))
    )
    (comp (ref "R50")
      (value "63k4/1%/500mW")
      (footprint "eagle-import:R0805")
      (libsource (lib "eagle-import") (part "R-EUR0805"))
    )
    (comp (ref "R51")
      (value "63k4/1%/500mW")
      (footprint "eagle-import:R0805")
      (libsource (lib "eagle-import") (part "R-EUR0805"))
    )
    (comp (ref "R52")
      (value "63k4/1%/500mW")
      (footprint "eagle-import:R0805")
      (libsource (lib "eagle-import") (part "R-EUR0805"))
    )
    (comp (ref "R53")
      (value "50R/1%")
      (footprint "eagle-import:R0603")
      (libsource (lib "eagle-import") (part "R-EUR0603"))
    )
    (comp (ref "R54")
      (value "100R")
      (footprint "eagle-import:R0603")
      (libsource (lib "eagle-import") (part "R-EUR0603"))
    )
    (comp (ref "R55")
      (value "4k7")
      (footprint "eagle-import:R0603")
      (libsource (lib "eagle-import") (part "R-EUR0603"))
    )
    (comp (ref "RL16")
      (value "G5LE-1-VD DC12")
      (footprint "eagle-import:SPDT")
      (libsource (lib "eagle-import") (part "G5LE-E"))
    )
    (comp (ref "X3")
      (value "AKL701_215")
      (footprint "eagle-import:AKL701_2_15")
      (libsource (lib "eagle-import") (part "AKL701_215"))
    )
    (comp (ref "X4")
      (value "CONSMA002-L-G")
      (footprint "eagle-import:SMA90_DIP")
      (libsource (lib "eagle-import") (part "SMACONNECTOR"))
    )
  )
  (nets
    (net (code "1") (name "+12V") (class "Default")
      (node (ref "C19") (pin "1") (pinfunction "1_1") (pintype "passive"))
      (node (ref "C20") (pin "1") (pinfunction "1_1") (pintype "passive"))
      (node (ref "C21") (pin "1") (pinfunction "1_1") (pintype "passive"))
      (node (ref "C22") (pin "1") (pinfunction "1_1") (pintype "passive"))
      (node (ref "C23") (pin "1") (pinfunction "1_1") (pintype "passive"))
      (node (ref "C24") (pin "1") (pinfunction "1_1") (pintype "passive"))
      (node (ref "C25") (pin "1") (pinfunction "1_1") (pintype "passive"))
      (node (ref "C26") (pin "1") (pinfunction "1_1") (pintype "passive"))
      (node (ref "C27") (pin "1") (pinfunction "1_1") (pintype "passive"))
      (node (ref "C28") (pin "1") (pinfunction "1_1") (pintype "passive"))
      (node (ref "C69") (pin "1") (pinfunction "1_1") (pintype "passive"))
      (node (ref "D10") (pin "C") (pinfunction "CATHODE_C") (pintype "bidirectional"))
      (node (ref "D11") (pin "C") (pinfunction "CATHODE_C") (pintype "bidirectional"))
      (node (ref "D15") (pin "C") (pinfunction "CATHODE_C") (pintype "bidirectional"))
      (node (ref "D16") (pin "C") (pinfunction "CATHODE_C") (pintype "bidirectional"))
      (node (ref "D19") (pin "C") (pinfunction "CATHODE_C") (pintype "bidirectional"))
      (node (ref "D20") (pin "C") (pinfunction "CATHODE_C") (pintype "bidirectional"))
      (node (ref "D21") (pin "C") (pinfunction "CATHODE_C") (pintype "bidirectional"))
      (node (ref "D22") (pin "C") (pinfunction "CATHODE_C") (pintype "bidirectional"))
      (node (ref "D23") (pin "C") (pinfunction "CATHODE_C") (pintype "bidirectional"))
      (node (ref "D29") (pin "C") (pinfunction "CATHODE_C") (pintype "bidirectional"))
      (node (ref "D9") (pin "C") (pinfunction "CATHODE_C") (pintype "bidirectional"))
      (node (ref "RL1") (pin "5") (pinfunction "5_5") (pintype "passive"))
      (node (ref "RL10") (pin "5") (pinfunction "5_5") (pintype "passive"))
      (node (ref "RL11") (pin "5") (pinfunction "5_5") (pintype "passive"))
      (node (ref "RL12") (pin "5") (pinfunction "5_5") (pintype "passive"))
      (node (ref "RL13") (pin "5") (pinfunction "5_5") (pintype "passive"))
      (node (ref "RL14") (pin "5") (pinfunction "5_5") (pintype "passive"))
      (node (ref "RL15") (pin "5") (pinfunction "5_5") (pintype "passive"))
      (node (ref "RL16") (pin "5") (pinfunction "5_5") (pintype "passive"))
      (node (ref "RL2") (pin "5") (pinfunction "5_5") (pintype "passive"))
      (node (ref "RL3") (pin "5") (pinfunction "5_5") (pintype "passive"))
      (node (ref "RL4") (pin "5") (pinfunction "5_5") (pintype "passive"))
      (node (ref "RL5") (pin "5") (pinfunction "5_5") (pintype "passive"))
      (node (ref "RL6") (pin "5") (pinfunction "5_5") (pintype "passive"))
      (node (ref "RL7") (pin "5") (pinfunction "5_5") (pintype "passive"))
      (node (ref "RL8") (pin "5") (pinfunction "5_5") (pintype "passive"))
      (node (ref "RL9") (pin "5") (pinfunction "5_5") (pintype "passive"))
      (node (ref "X2") (pin "2") (pinfunction "2_2") (pintype "passive"))
    )
    (net (code "2") (name "FILT_CAP_CTRL_0") (class "Default")
      (node (ref "P2") (pin "1") (pinfunction "1_1") (pintype "passive"))
      (node (ref "R13") (pin "1") (pinfunction "1_1") (pintype "passive"))
      (node (ref "R16") (pin "2") (pinfunction "2_2") (pintype "passive"))
    )
    (net (code "3") (name "FILT_CAP_CTRL_1") (class "Default")
      (node (ref "P2") (pin "2") (pinfunction "2_2") (pintype "passive"))
      (node (ref "R14") (pin "1") (pinfunction "1_1") (pintype "passive"))
      (node (ref "R17") (pin "2") (pinfunction "2_2") (pintype "passive"))
    )
    (net (code "4") (name "FILT_CAP_CTRL_2") (class "Default")
      (node (ref "P2") (pin "3") (pinfunction "3_3") (pintype "passive"))
      (node (ref "R15") (pin "1") (pinfunction "1_1") (pintype "passive"))
      (node (ref "R18") (pin "2") (pinfunction "2_2") (pintype "passive"))
    )
    (net (code "5") (name "FILT_CAP_CTRL_3") (class "Default")
      (node (ref "P2") (pin "4") (pinfunction "4_4") (pintype "passive"))
      (node (ref "R19") (pin "1") (pinfunction "1_1") (pintype "passive"))
      (node (ref "R21") (pin "2") (pinfunction "2_2") (pintype "passive"))
    )
    (net (code "6") (name "FILT_CAP_CTRL_4") (class "Default")
      (node (ref "P2") (pin "5") (pinfunction "5_5") (pintype "passive"))
      (node (ref "R20") (pin "1") (pinfunction "1_1") (pintype "passive"))
      (node (ref "R22") (pin "2") (pinfunction "2_2") (pintype "passive"))
    )
    (net (code "7") (name "FILT_INDUCT_CTRL_0") (class "Default")
      (node (ref "P2") (pin "6") (pinfunction "6_6") (pintype "passive"))
      (node (ref "R23") (pin "1") (pinfunction "1_1") (pintype "passive"))
      (node (ref "R28") (pin "2") (pinfunction "2_2") (pintype "passive"))
    )
    (net (code "8") (name "FILT_INDUCT_CTRL_1") (class "Default")
      (node (ref "P2") (pin "7") (pinfunction "7_7") (pintype "passive"))
      (node (ref "R24") (pin "1") (pinfunction "1_1") (pintype "passive"))
      (node (ref "R29") (pin "2") (pinfunction "2_2") (pintype "passive"))
    )
    (net (code "9") (name "FILT_INDUCT_CTRL_2") (class "Default")
      (node (ref "P2") (pin "8") (pinfunction "8_8") (pintype "passive"))
      (node (ref "R25") (pin "1") (pinfunction "1_1") (pintype "passive"))
      (node (ref "R30") (pin "2") (pinfunction "2_2") (pintype "passive"))
    )
    (net (code "10") (name "FILT_INDUCT_CTRL_3") (class "Default")
      (node (ref "P2") (pin "9") (pinfunction "9_9") (pintype "passive"))
      (node (ref "R26") (pin "1") (pinfunction "1_1") (pintype "passive"))
      (node (ref "R31") (pin "2") (pinfunction "2_2") (pintype "passive"))
    )
    (net (code "11") (name "FILT_INDUCT_CTRL_4") (class "Default")
      (node (ref "P2") (pin "10") (pinfunction "10_10") (pintype "passive"))
      (node (ref "R27") (pin "1") (pinfunction "1_1") (pintype "passive"))
      (node (ref "R32") (pin "2") (pinfunction "2_2") (pintype "passive"))
    )
    (net (code "12") (name "FWD") (class "Default")
      (node (ref "C10") (pin "1") (pinfunction "1_1") (pintype "passive"))
      (node (ref "C18") (pin "1") (pinfunction "1_1") (pintype "passive"))
      (node (ref "D3") (pin "A") (pinfunction "ANODE_A") (pintype "bidirectional"))
      (node (ref "D7") (pin "C") (pinfunction "CATHODE_C") (pintype "bidirectional"))
      (node (ref "R12") (pin "2") (pinfunction "2_2") (pintype "passive"))
      (node (ref "R3") (pin "2") (pinfunction "2_2") (pintype "passive"))
      (node (ref "U1") (pin "3") (pinfunction "VIN_3") (pintype "input"))
    )
    (net (code "13") (name "GND") (class "Default")
      (node (ref "C19") (pin "2") (pinfunction "2_2") (pintype "passive"))
      (node (ref "C20") (pin "2") (pinfunction "2_2") (pintype "passive"))
      (node (ref "C21") (pin "2") (pinfunction "2_2") (pintype "passive"))
      (node (ref "C22") (pin "2") (pinfunction "2_2") (pintype "passive"))
      (node (ref "C23") (pin "2") (pinfunction "2_2") (pintype "passive"))
      (node (ref "C24") (pin "2") (pinfunction "2_2") (pintype "passive"))
      (node (ref "C25") (pin "2") (pinfunction "2_2") (pintype "passive"))
      (node (ref "C26") (pin "2") (pinfunction "2_2") (pintype "passive"))
      (node (ref "C27") (pin "2") (pinfunction "2_2") (pintype "passive"))
      (node (ref "C28") (pin "2") (pinfunction "2_2") (pintype "passive"))
      (node (ref "C69") (pin "2") (pinfunction "2_2") (pintype "passive"))
      (node (ref "D12") (pin "A") (pinfunction "ANODE_A") (pintype "bidirectional"))
      (node (ref "D13") (pin "A") (pinfunction "ANODE_A") (pintype "bidirectional"))
      (node (ref "D14") (pin "A") (pinfunction "ANODE_A") (pintype "bidirectional"))
      (node (ref "D17") (pin "A") (pinfunction "ANODE_A") (pintype "bidirectional"))
      (node (ref "D18") (pin "A") (pinfunction "ANODE_A") (pintype "bidirectional"))
      (node (ref "D24") (pin "A") (pinfunction "ANODE_A") (pintype "bidirectional"))
      (node (ref "D25") (pin "A") (pinfunction "ANODE_A") (pintype "bidirectional"))
      (node (ref "D26") (pin "A") (pinfunction "ANODE_A") (pintype "bidirectional"))
      (node (ref "D27") (pin "A") (pinfunction "ANODE_A") (pintype "bidirectional"))
      (node (ref "D28") (pin "A") (pinfunction "ANODE_A") (pintype "bidirectional"))
      (node (ref "D30") (pin "A") (pinfunction "ANODE_A") (pintype "bidirectional"))
      (node (ref "P2") (pin "12") (pinfunction "12_12") (pintype "passive"))
      (node (ref "P2") (pin "13") (pinfunction "13_13") (pintype "passive"))
      (node (ref "P2") (pin "14") (pinfunction "14_14") (pintype "passive"))
      (node (ref "P2") (pin "15") (pinfunction "15_15") (pintype "passive"))
      (node (ref "P2") (pin "16") (pinfunction "16_16") (pintype "passive"))
      (node (ref "P2") (pin "17") (pinfunction "17_17") (pintype "passive"))
      (node (ref "P2") (pin "18") (pinfunction "18_18") (pintype "passive"))
      (node (ref "P2") (pin "19") (pinfunction "19_19") (pintype "passive"))
      (node (ref "P2") (pin "20") (pinfunction "20_20") (pintype "passive"))
      (node (ref "Q1") (pin "2") (pinfunction "S_2") (pintype "bidirectional"))
      (node (ref "Q10") (pin "2") (pinfunction "S_2") (pintype "bidirectional"))
      (node (ref "Q11") (pin "2") (pinfunction "S_2") (pintype "bidirectional"))
      (node (ref "Q2") (pin "2") (pinfunction "S_2") (pintype "bidirectional"))
      (node (ref "Q3") (pin "2") (pinfunction "S_2") (pintype "bidirectional"))
      (node (ref "Q4") (pin "2") (pinfunction "S_2") (pintype "bidirectional"))
      (node (ref "Q5") (pin "2") (pinfunction "S_2") (pintype "bidirectional"))
      (node (ref "Q6") (pin "2") (pinfunction "S_2") (pintype "bidirectional"))
      (node (ref "Q7") (pin "2") (pinfunction "S_2") (pintype "bidirectional"))
      (node (ref "Q8") (pin "2") (pinfunction "S_2") (pintype "bidirectional"))
      (node (ref "Q9") (pin "2") (pinfunction "S_2") (pintype "bidirectional"))
      (node (ref "R16") (pin "1") (pinfunction "1_1") (pintype "passive"))
      (node (ref "R17") (pin "1") (pinfunction "1_1") (pintype "passive"))
      (node (ref "R18") (pin "1") (pinfunction "1_1") (pintype "passive"))
      (node (ref "R21") (pin "1") (pinfunction "1_1") (pintype "passive"))
      (node (ref "R22") (pin "1") (pinfunction "1_1") (pintype "passive"))
      (node (ref "R28") (pin "1") (pinfunction "1_1") (pintype "passive"))
      (node (ref "R29") (pin "1") (pinfunction "1_1") (pintype "passive"))
      (node (ref "R30") (pin "1") (pinfunction "1_1") (pintype "passive"))
      (node (ref "R31") (pin "1") (pinfunction "1_1") (pintype "passive"))
      (node (ref "R32") (pin "1") (pinfunction "1_1") (pintype "passive"))
      (node (ref "R55") (pin "1") (pinfunction "1_1") (pintype "passive"))
      (node (ref "X2") (pin "1") (pinfunction "1_1") (pintype "passive"))
    )
    (net (code "14") (name "Net-(C10-Pad2)") (class "Default")
      (node (ref "C10") (pin "2") (pinfunction "2_2") (pintype "passive"))
      (node (ref "C12") (pin "1") (pinfunction "1_1") (pintype "passive"))
    )
    (net (code "15") (name "Net-(C11-Pad1)") (class "Default")
      (node (ref "C11") (pin "1") (pinfunction "1_1") (pintype "passive"))
      (node (ref "C9") (pin "2") (pinfunction "2_2") (pintype "passive"))
    )
    (net (code "16") (name "Net-(C13-Pad2)") (class "Default")
      (node (ref "C13") (pin "2") (pinfunction "2_2") (pintype "passive"))
      (node (ref "C15") (pin "1") (pinfunction "1_1") (pintype "passive"))
    )
    (net (code "17") (name "Net-(C14-Pad2)") (class "Default")
      (node (ref "C14") (pin "2") (pinfunction "2_2") (pintype "passive"))
      (node (ref "C16") (pin "1") (pinfunction "1_1") (pintype "passive"))
    )
    (net (code "18") (name "Net-(C29-Pad1)") (class "Default")
      (node (ref "C29") (pin "1") (pinfunction "1_1") (pintype "passive"))
      (node (ref "C30") (pin "1") (pinfunction "1_1") (pintype "passive"))
      (node (ref "RL1") (pin "1") (pinfunction "1_1") (pintype "passive"))
    )
    (net (code "19") (name "Net-(C29-Pad2)") (class "Default")
      (node (ref "C29") (pin "2") (pinfunction "2_2") (pintype "passive"))
      (node (ref "C39") (pin "1") (pinfunction "1_1") (pintype "passive"))
    )
    (net (code "20") (name "Net-(C30-Pad2)") (class "Default")
      (node (ref "C30") (pin "2") (pinfunction "2_2") (pintype "passive"))
      (node (ref "C40") (pin "1") (pinfunction "1_1") (pintype "passive"))
    )
    (net (code "21") (name "Net-(C31-Pad1)") (class "Default")
      (node (ref "C31") (pin "1") (pinfunction "1_1") (pintype "passive"))
      (node (ref "C32") (pin "1") (pinfunction "1_1") (pintype "passive"))
      (node (ref "RL3") (pin "1") (pinfunction "1_1") (pintype "passive"))
    )
    (net (code "22") (name "Net-(C31-Pad2)") (class "Default")
      (node (ref "C31") (pin "2") (pinfunction "2_2") (pintype "passive"))
      (node (ref "C41") (pin "1") (pinfunction "1_1") (pintype "passive"))
    )
    (net (code "23") (name "Net-(C32-Pad2)") (class "Default")
      (node (ref "C32") (pin "2") (pinfunction "2_2") (pintype "passive"))
      (node (ref "C42") (pin "1") (pinfunction "1_1") (pintype "passive"))
    )
    (net (code "24") (name "Net-(C33-Pad1)") (class "Default")
      (node (ref "C33") (pin "1") (pinfunction "1_1") (pintype "passive"))
      (node (ref "C34") (pin "1") (pinfunction "1_1") (pintype "passive"))
      (node (ref "RL5") (pin "1") (pinfunction "1_1") (pintype "passive"))
    )
    (net (code "25") (name "Net-(C33-Pad2)") (class "Default")
      (node (ref "C33") (pin "2") (pinfunction "2_2") (pintype "passive"))
      (node (ref "C43") (pin "1") (pinfunction "1_1") (pintype "passive"))
    )
    (net (code "26") (name "Net-(C34-Pad2)") (class "Default")
      (node (ref "C34") (pin "2") (pinfunction "2_2") (pintype "passive"))
      (node (ref "C44") (pin "1") (pinfunction "1_1") (pintype "passive"))
    )
    (net (code "27") (name "Net-(C35-Pad1)") (class "Default")
      (node (ref "C35") (pin "1") (pinfunction "1_1") (pintype "passive"))
      (node (ref "C36") (pin "1") (pinfunction "1_1") (pintype "passive"))
      (node (ref "RL7") (pin "1") (pinfunction "1_1") (pintype "passive"))
    )
    (net (code "28") (name "Net-(C35-Pad2)") (class "Default")
      (node (ref "C35") (pin "2") (pinfunction "2_2") (pintype "passive"))
      (node (ref "C45") (pin "1") (pinfunction "1_1") (pintype "passive"))
    )
    (net (code "29") (name "Net-(C36-Pad2)") (class "Default")
      (node (ref "C36") (pin "2") (pinfunction "2_2") (pintype "passive"))
      (node (ref "C46") (pin "1") (pinfunction "1_1") (pintype "passive"))
    )
    (net (code "30") (name "Net-(C37-Pad1)") (class "Default")
      (node (ref "C37") (pin "1") (pinfunction "1_1") (pintype "passive"))
      (node (ref "C38") (pin "1") (pinfunction "1_1") (pintype "passive"))
      (node (ref "RL9") (pin "1") (pinfunction "1_1") (pintype "passive"))
    )
    (net (code "31") (name "Net-(C37-Pad2)") (class "Default")
      (node (ref "C37") (pin "2") (pinfunction "2_2") (pintype "passive"))
      (node (ref "C47") (pin "1") (pinfunction "1_1") (pintype "passive"))
    )
    (net (code "32") (name "Net-(C38-Pad2)") (class "Default")
      (node (ref "C38") (pin "2") (pinfunction "2_2") (pintype "passive"))
      (node (ref "C48") (pin "1") (pinfunction "1_1") (pintype "passive"))
    )
    (net (code "33") (name "Net-(C49-Pad1)") (class "Default")
      (node (ref "C49") (pin "1") (pinfunction "1_1") (pintype "passive"))
      (node (ref "C50") (pin "1") (pinfunction "1_1") (pintype "passive"))
      (node (ref "RL2") (pin "1") (pinfunction "1_1") (pintype "passive"))
    )
    (net (code "34") (name "Net-(C49-Pad2)") (class "Default")
      (node (ref "C49") (pin "2") (pinfunction "2_2") (pintype "passive"))
      (node (ref "C59") (pin "1") (pinfunction "1_1") (pintype "passive"))
    )
    (net (code "35") (name "Net-(C50-Pad2)") (class "Default")
      (node (ref "C50") (pin "2") (pinfunction "2_2") (pintype "passive"))
      (node (ref "C60") (pin "1") (pinfunction "1_1") (pintype "passive"))
    )
    (net (code "36") (name "Net-(C51-Pad1)") (class "Default")
      (node (ref "C51") (pin "1") (pinfunction "1_1") (pintype "passive"))
      (node (ref "C52") (pin "1") (pinfunction "1_1") (pintype "passive"))
      (node (ref "RL4") (pin "1") (pinfunction "1_1") (pintype "passive"))
    )
    (net (code "37") (name "Net-(C51-Pad2)") (class "Default")
      (node (ref "C51") (pin "2") (pinfunction "2_2") (pintype "passive"))
      (node (ref "C61") (pin "1") (pinfunction "1_1") (pintype "passive"))
    )
    (net (code "38") (name "Net-(C52-Pad2)") (class "Default")
      (node (ref "C52") (pin "2") (pinfunction "2_2") (pintype "passive"))
      (node (ref "C62") (pin "1") (pinfunction "1_1") (pintype "passive"))
    )
    (net (code "39") (name "Net-(C53-Pad1)") (class "Default")
      (node (ref "C53") (pin "1") (pinfunction "1_1") (pintype "passive"))
      (node (ref "C54") (pin "1") (pinfunction "1_1") (pintype "passive"))
      (node (ref "RL6") (pin "1") (pinfunction "1_1") (pintype "passive"))
    )
    (net (code "40") (name "Net-(C53-Pad2)") (class "Default")
      (node (ref "C53") (pin "2") (pinfunction "2_2") (pintype "passive"))
      (node (ref "C63") (pin "1") (pinfunction "1_1") (pintype "passive"))
    )
    (net (code "41") (name "Net-(C54-Pad2)") (class "Default")
      (node (ref "C54") (pin "2") (pinfunction "2_2") (pintype "passive"))
      (node (ref "C64") (pin "1") (pinfunction "1_1") (pintype "passive"))
    )
    (net (code "42") (name "Net-(C55-Pad1)") (class "Default")
      (node (ref "C55") (pin "1") (pinfunction "1_1") (pintype "passive"))
      (node (ref "C56") (pin "1") (pinfunction "1_1") (pintype "passive"))
      (node (ref "RL8") (pin "1") (pinfunction "1_1") (pintype "passive"))
    )
    (net (code "43") (name "Net-(C55-Pad2)") (class "Default")
      (node (ref "C55") (pin "2") (pinfunction "2_2") (pintype "passive"))
      (node (ref "C65") (pin "1") (pinfunction "1_1") (pintype "passive"))
    )
    (net (code "44") (name "Net-(C56-Pad2)") (class "Default")
      (node (ref "C56") (pin "2") (pinfunction "2_2") (pintype "passive"))
      (node (ref "C66") (pin "1") (pinfunction "1_1") (pintype "passive"))
    )
    (net (code "45") (name "Net-(C57-Pad1)") (class "Default")
      (node (ref "C57") (pin "1") (pinfunction "1_1") (pintype "passive"))
      (node (ref "C58") (pin "1") (pinfunction "1_1") (pintype "passive"))
      (node (ref "RL10") (pin "1") (pinfunction "1_1") (pintype "passive"))
    )
    (net (code "46") (name "Net-(C57-Pad2)") (class "Default")
      (node (ref "C57") (pin "2") (pinfunction "2_2") (pintype "passive"))
      (node (ref "C67") (pin "1") (pinfunction "1_1") (pintype "passive"))
    )
    (net (code "47") (name "Net-(C58-Pad2)") (class "Default")
      (node (ref "C58") (pin "2") (pinfunction "2_2") (pintype "passive"))
      (node (ref "C68") (pin "1") (pinfunction "1_1") (pintype "passive"))
    )
    (net (code "48") (name "Net-(D1-CATHODE)") (class "Default")
      (node (ref "D1") (pin "C") (pinfunction "CATHODE_C") (pintype "bidirectional"))
      (node (ref "D2") (pin "A") (pinfunction "ANODE_A") (pintype "bidirectional"))
    )
    (net (code "49") (name "Net-(D2-CATHODE)") (class "Default")
      (node (ref "C9") (pin "1") (pinfunction "1_1") (pintype "passive"))
      (node (ref "D2") (pin "C") (pinfunction "CATHODE_C") (pintype "bidirectional"))
      (node (ref "R1") (pin "1") (pinfunction "1_1") (pintype "passive"))
    )
    (net (code "50") (name "Net-(D5-ANODE)") (class "Default")
      (node (ref "D5") (pin "A") (pinfunction "ANODE_A") (pintype "bidirectional"))
      (node (ref "R7") (pin "1") (pinfunction "1_1") (pintype "passive"))
      (node (ref "T1") (pin "T1-1") (pinfunction "L1-1_T1-1") (pintype "bidirectional"))
    )
    (net (code "51") (name "Net-(D5-CATHODE)") (class "Default")
      (node (ref "D5") (pin "C") (pinfunction "CATHODE_C") (pintype "bidirectional"))
      (node (ref "D6") (pin "A") (pinfunction "ANODE_A") (pintype "bidirectional"))
    )
    (net (code "52") (name "Net-(D6-CATHODE)") (class "Default")
      (node (ref "C15") (pin "2") (pinfunction "2_2") (pintype "passive"))
      (node (ref "D6") (pin "C") (pinfunction "CATHODE_C") (pintype "bidirectional"))
      (node (ref "R8") (pin "1") (pinfunction "1_1") (pintype "passive"))
    )
    (net (code "53") (name "Net-(D10-ANODE)") (class "Default")
      (node (ref "D10") (pin "A") (pinfunction "ANODE_A") (pintype "bidirectional"))
      (node (ref "D13") (pin "C") (pinfunction "CATHODE_C") (pintype "bidirectional"))
      (node (ref "Q2") (pin "3") (pinfunction "D_3") (pintype "bidirectional"))
      (node (ref "RL3") (pin "2") (pinfunction "2_2") (pintype "passive"))
      (node (ref "RL4") (pin "2") (pinfunction "2_2") (pintype "passive"))
    )
    (net (code "54") (name "Net-(D11-ANODE)") (class "Default")
      (node (ref "D11") (pin "A") (pinfunction "ANODE_A") (pintype "bidirectional"))
      (node (ref "D14") (pin "C") (pinfunction "CATHODE_C") (pintype "bidirectional"))
      (node (ref "Q3") (pin "3") (pinfunction "D_3") (pintype "bidirectional"))
      (node (ref "RL5") (pin "2") (pinfunction "2_2") (pintype "passive"))
      (node (ref "RL6") (pin "2") (pinfunction "2_2") (pintype "passive"))
    )
    (net (code "55") (name "Net-(D12-CATHODE)") (class "Default")
      (node (ref "D12") (pin "C") (pinfunction "CATHODE_C") (pintype "bidirectional"))
      (node (ref "D9") (pin "A") (pinfunction "ANODE_A") (pintype "bidirectional"))
      (node (ref "Q1") (pin "3") (pinfunction "D_3") (pintype "bidirectional"))
      (node (ref "RL1") (pin "2") (pinfunction "2_2") (pintype "passive"))
      (node (ref "RL2") (pin "2") (pinfunction "2_2") (pintype "passive"))
    )
    (net (code "56") (name "Net-(D15-ANODE)") (class "Default")
      (node (ref "D15") (pin "A") (pinfunction "ANODE_A") (pintype "bidirectional"))
      (node (ref "D17") (pin "C") (pinfunction "CATHODE_C") (pintype "bidirectional"))
      (node (ref "Q4") (pin "3") (pinfunction "D_3") (pintype "bidirectional"))
      (node (ref "RL7") (pin "2") (pinfunction "2_2") (pintype "passive"))
      (node (ref "RL8") (pin "2") (pinfunction "2_2") (pintype "passive"))
    )
    (net (code "57") (name "Net-(D16-ANODE)") (class "Default")
      (node (ref "D16") (pin "A") (pinfunction "ANODE_A") (pintype "bidirectional"))
      (node (ref "D18") (pin "C") (pinfunction "CATHODE_C") (pintype "bidirectional"))
      (node (ref "Q5") (pin "3") (pinfunction "D_3") (pintype "bidirectional"))
      (node (ref "RL10") (pin "2") (pinfunction "2_2") (pintype "passive"))
      (node (ref "RL9") (pin "2") (pinfunction "2_2") (pintype "passive"))
    )
    (net (code "58") (name "Net-(D19-ANODE)") (class "Default")
      (node (ref "D19") (pin "A") (pinfunction "ANODE_A") (pintype "bidirectional"))
      (node (ref "D24") (pin "C") (pinfunction "CATHODE_C") (pintype "bidirectional"))
      (node (ref "Q6") (pin "3") (pinfunction "D_3") (pintype "bidirectional"))
      (node (ref "RL11") (pin "2") (pinfunction "2_2") (pintype "passive"))
    )
    (net (code "59") (name "Net-(D20-ANODE)") (class "Default")
      (node (ref "D20") (pin "A") (pinfunction "ANODE_A") (pintype "bidirectional"))
      (node (ref "D25") (pin "C") (pinfunction "CATHODE_C") (pintype "bidirectional"))
      (node (ref "Q7") (pin "3") (pinfunction "D_3") (pintype "bidirectional"))
      (node (ref "RL12") (pin "2") (pinfunction "2_2") (pintype "passive"))
    )
    (net (code "60") (name "Net-(D21-ANODE)") (class "Default")
      (node (ref "D21") (pin "A") (pinfunction "ANODE_A") (pintype "bidirectional"))
      (node (ref "D26") (pin "C") (pinfunction "CATHODE_C") (pintype "bidirectional"))
      (node (ref "Q8") (pin "3") (pinfunction "D_3") (pintype "bidirectional"))
      (node (ref "RL13") (pin "2") (pinfunction "2_2") (pintype "passive"))
    )
    (net (code "61") (name "Net-(D22-ANODE)") (class "Default")
      (node (ref "D22") (pin "A") (pinfunction "ANODE_A") (pintype "bidirectional"))
      (node (ref "D27") (pin "C") (pinfunction "CATHODE_C") (pintype "bidirectional"))
      (node (ref "Q9") (pin "3") (pinfunction "D_3") (pintype "bidirectional"))
      (node (ref "RL14") (pin "2") (pinfunction "2_2") (pintype "passive"))
    )
    (net (code "62") (name "Net-(D23-ANODE)") (class "Default")
      (node (ref "D23") (pin "A") (pinfunction "ANODE_A") (pintype "bidirectional"))
      (node (ref "D28") (pin "C") (pinfunction "CATHODE_C") (pintype "bidirectional"))
      (node (ref "Q10") (pin "3") (pinfunction "D_3") (pintype "bidirectional"))
      (node (ref "RL15") (pin "2") (pinfunction "2_2") (pintype "passive"))
    )
    (net (code "63") (name "Net-(D29-ANODE)") (class "Default")
      (node (ref "D29") (pin "A") (pinfunction "ANODE_A") (pintype "bidirectional"))
      (node (ref "D30") (pin "C") (pinfunction "CATHODE_C") (pintype "bidirectional"))
      (node (ref "Q11") (pin "3") (pinfunction "D_3") (pintype "bidirectional"))
      (node (ref "RL16") (pin "2") (pinfunction "2_2") (pintype "passive"))
    )
    (net (code "64") (name "Net-(L1-Pad2)") (class "Default")
      (node (ref "L1") (pin "2") (pinfunction "2_2") (pintype "passive"))
      (node (ref "L2") (pin "1") (pinfunction "1_1") (pintype "passive"))
      (node (ref "RL11") (pin "3") (pinfunction "3_3") (pintype "passive"))
      (node (ref "RL12") (pin "1") (pinfunction "1_1") (pintype "passive"))
    )
    (net (code "65") (name "Net-(L2-Pad2)") (class "Default")
      (node (ref "L2") (pin "2") (pinfunction "2_2") (pintype "passive"))
      (node (ref "L3") (pin "1") (pinfunction "1_1") (pintype "passive"))
      (node (ref "RL12") (pin "3") (pinfunction "3_3") (pintype "passive"))
      (node (ref "RL13") (pin "1") (pinfunction "1_1") (pintype "passive"))
    )
    (net (code "66") (name "Net-(L3-Pad2)") (class "Default")
      (node (ref "L3") (pin "2") (pinfunction "2_2") (pintype "passive"))
      (node (ref "L4") (pin "1") (pinfunction "1_1") (pintype "passive"))
      (node (ref "RL13") (pin "3") (pinfunction "3_3") (pintype "passive"))
      (node (ref "RL14") (pin "1") (pinfunction "1_1") (pintype "passive"))
    )
    (net (code "67") (name "Net-(L4-Pad2)") (class "Default")
      (node (ref "L4") (pin "2") (pinfunction "2_2") (pintype "passive"))
      (node (ref "L5") (pin "1") (pinfunction "1_1") (pintype "passive"))
      (node (ref "RL14") (pin "3") (pinfunction "3_3") (pintype "passive"))
      (node (ref "RL15") (pin "1") (pinfunction "1_1") (pintype "passive"))
    )
    (net (code "68") (name "Net-(Q1-G)") (class "Default")
      (node (ref "Q1") (pin "1") (pinfunction "G_1") (pintype "bidirectional"))
      (node (ref "R13") (pin "2") (pinfunction "2_2") (pintype "passive"))
    )
    (net (code "69") (name "Net-(Q2-G)") (class "Default")
      (node (ref "Q2") (pin "1") (pinfunction "G_1") (pintype "bidirectional"))
      (node (ref "R14") (pin "2") (pinfunction "2_2") (pintype "passive"))
    )
    (net (code "70") (name "Net-(Q3-G)") (class "Default")
      (node (ref "Q3") (pin "1") (pinfunction "G_1") (pintype "bidirectional"))
      (node (ref "R15") (pin "2") (pinfunction "2_2") (pintype "passive"))
    )
    (net (code "71") (name "Net-(Q4-G)") (class "Default")
      (node (ref "Q4") (pin "1") (pinfunction "G_1") (pintype "bidirectional"))
      (node (ref "R19") (pin "2") (pinfunction "2_2") (pintype "passive"))
    )
    (net (code "72") (name "Net-(Q5-G)") (class "Default")
      (node (ref "Q5") (pin "1") (pinfunction "G_1") (pintype "bidirectional"))
      (node (ref "R20") (pin "2") (pinfunction "2_2") (pintype "passive"))
    )
    (net (code "73") (name "Net-(Q6-G)") (class "Default")
      (node (ref "Q6") (pin "1") (pinfunction "G_1") (pintype "bidirectional"))
      (node (ref "R23") (pin "2") (pinfunction "2_2") (pintype "passive"))
    )
    (net (code "74") (name "Net-(Q7-G)") (class "Default")
      (node (ref "Q7") (pin "1") (pinfunction "G_1") (pintype "bidirectional"))
      (node (ref "R24") (pin "2") (pinfunction "2_2") (pintype "passive"))
    )
    (net (code "75") (name "Net-(Q8-G)") (class "Default")
      (node (ref "Q8") (pin "1") (pinfunction "G_1") (pintype "bidirectional"))
      (node (ref "R25") (pin "2") (pinfunction "2_2") (pintype "passive"))
    )
    (net (code "76") (name "Net-(Q9-G)") (class "Default")
      (node (ref "Q9") (pin "1") (pinfunction "G_1") (pintype "bidirectional"))
      (node (ref "R26") (pin "2") (pinfunction "2_2") (pintype "passive"))
    )
    (net (code "77") (name "Net-(Q10-G)") (class "Default")
      (node (ref "Q10") (pin "1") (pinfunction "G_1") (pintype "bidirectional"))
      (node (ref "R27") (pin "2") (pinfunction "2_2") (pintype "passive"))
    )
    (net (code "78") (name "Net-(Q11-G)") (class "Default")
      (node (ref "Q11") (pin "1") (pinfunction "G_1") (pintype "bidirectional"))
      (node (ref "R54") (pin "2") (pinfunction "2_2") (pintype "passive"))
    )
    (net (code "79") (name "Net-(R1-Pad2)") (class "Default")
      (node (ref "R1") (pin "2") (pinfunction "2_2") (pintype "passive"))
      (node (ref "R2") (pin "1") (pinfunction "1_1") (pintype "passive"))
    )
    (net (code "80") (name "Net-(R2-Pad2)") (class "Default")
      (node (ref "R2") (pin "2") (pinfunction "2_2") (pintype "passive"))
      (node (ref "R3") (pin "1") (pinfunction "1_1") (pintype "passive"))
    )
    (net (code "81") (name "Net-(R4-Pad1)") (class "Default")
      (node (ref "R4") (pin "1") (pinfunction "1_1") (pintype "passive"))
      (node (ref "R5") (pin "2") (pinfunction "2_2") (pintype "passive"))
    )
    (net (code "82") (name "Net-(R6-Pad1)") (class "Default")
      (node (ref "R6") (pin "1") (pinfunction "1_1") (pintype "passive"))
      (node (ref "R7") (pin "2") (pinfunction "2_2") (pintype "passive"))
    )
    (net (code "83") (name "Net-(R8-Pad2)") (class "Default")
      (node (ref "R8") (pin "2") (pinfunction "2_2") (pintype "passive"))
      (node (ref "R9") (pin "1") (pinfunction "1_1") (pintype "passive"))
    )
    (net (code "84") (name "Net-(R10-Pad1)") (class "Default")
      (node (ref "R10") (pin "1") (pinfunction "1_1") (pintype "passive"))
      (node (ref "R9") (pin "2") (pinfunction "2_2") (pintype "passive"))
    )
    (net (code "85") (name "Net-(R33-Pad2)") (class "Default")
      (node (ref "R33") (pin "2") (pinfunction "2_2") (pintype "passive"))
      (node (ref "R34") (pin "1") (pinfunction "1_1") (pintype "passive"))
    )
    (net (code "86") (name "Net-(R34-Pad2)") (class "Default")
      (node (ref "R34") (pin "2") (pinfunction "2_2") (pintype "passive"))
      (node (ref "R35") (pin "1") (pinfunction "1_1") (pintype "passive"))
    )
    (net (code "87") (name "Net-(R35-Pad2)") (class "Default")
      (node (ref "R35") (pin "2") (pinfunction "2_2") (pintype "passive"))
      (node (ref "R36") (pin "1") (pinfunction "1_1") (pintype "passive"))
    )
    (net (code "88") (name "Net-(R36-Pad2)") (class "Default")
      (node (ref "R36") (pin "2") (pinfunction "2_2") (pintype "passive"))
      (node (ref "R40") (pin "2") (pinfunction "2_2") (pintype "passive"))
    )
    (net (code "89") (name "Net-(R37-Pad1)") (class "Default")
      (node (ref "R37") (pin "1") (pinfunction "1_1") (pintype "passive"))
      (node (ref "R41") (pin "1") (pinfunction "1_1") (pintype "passive"))
    )
    (net (code "90") (name "Net-(R37-Pad2)") (class "Default")
      (node (ref "R37") (pin "2") (pinfunction "2_2") (pintype "passive"))
      (node (ref "R38") (pin "1") (pinfunction "1_1") (pintype "passive"))
    )
    (net (code "91") (name "Net-(R38-Pad2)") (class "Default")
      (node (ref "R38") (pin "2") (pinfunction "2_2") (pintype "passive"))
      (node (ref "R39") (pin "1") (pinfunction "1_1") (pintype "passive"))
    )
    (net (code "92") (name "Net-(R39-Pad2)") (class "Default")
      (node (ref "R39") (pin "2") (pinfunction "2_2") (pintype "passive"))
      (node (ref "R40") (pin "1") (pinfunction "1_1") (pintype "passive"))
    )
    (net (code "93") (name "Net-(R41-Pad2)") (class "Default")
      (node (ref "R41") (pin "2") (pinfunction "2_2") (pintype "passive"))
      (node (ref "R42") (pin "1") (pinfunction "1_1") (pintype "passive"))
    )
    (net (code "94") (name "Net-(R42-Pad2)") (class "Default")
      (node (ref "R42") (pin "2") (pinfunction "2_2") (pintype "passive"))
      (node (ref "R43") (pin "1") (pinfunction "1_1") (pintype "passive"))
    )
    (net (code "95") (name "Net-(R43-Pad2)") (class "Default")
      (node (ref "R43") (pin "2") (pinfunction "2_2") (pintype "passive"))
      (node (ref "R44") (pin "1") (pinfunction "1_1") (pintype "passive"))
    )
    (net (code "96") (name "Net-(R44-Pad2)") (class "Default")
      (node (ref "R44") (pin "2") (pinfunction "2_2") (pintype "passive"))
      (node (ref "R48") (pin "2") (pinfunction "2_2") (pintype "passive"))
    )
    (net (code "97") (name "Net-(R45-Pad1)") (class "Default")
      (node (ref "R45") (pin "1") (pinfunction "1_1") (pintype "passive"))
      (node (ref "R49") (pin "1") (pinfunction "1_1") (pintype "passive"))
    )
    (net (code "98") (name "Net-(R45-Pad2)") (class "Default")
      (node (ref "R45") (pin "2") (pinfunction "2_2") (pintype "passive"))
      (node (ref "R46") (pin "1") (pinfunction "1_1") (pintype "passive"))
    )
    (net (code "99") (name "Net-(R46-Pad2)") (class "Default")
      (node (ref "R46") (pin "2") (pinfunction "2_2") (pintype "passive"))
      (node (ref "R47") (pin "1") (pinfunction "1_1") (pintype "passive"))
    )
    (net (code "100") (name "Net-(R47-Pad2)") (class "Default")
      (node (ref "R47") (pin "2") (pinfunction "2_2") (pintype "passive"))
      (node (ref "R48") (pin "1") (pinfunction "1_1") (pintype "passive"))
    )
    (net (code "101") (name "Net-(R49-Pad2)") (class "Default")
      (node (ref "R49") (pin "2") (pinfunction "2_2") (pintype "passive"))
      (node (ref "R50") (pin "1") (pinfunction "1_1") (pintype "passive"))
    )
    (net (code "102") (name "Net-(R50-Pad2)") (class "Default")
      (node (ref "R50") (pin "2") (pinfunction "2_2") (pintype "passive"))
      (node (ref "R51") (pin "1") (pinfunction "1_1") (pintype "passive"))
    )
    (net (code "103") (name "Net-(R51-Pad2)") (class "Default")
      (node (ref "R51") (pin "2") (pinfunction "2_2") (pintype "passive"))
      (node (ref "R52") (pin "1") (pinfunction "1_1") (pintype "passive"))
    )
    (net (code "104") (name "Net-(T1-C2-2)") (class "Default")
      (node (ref "T1") (pin "L2-2") (pinfunction "C2-2_L2-2") (pintype "bidirectional"))
      (node (ref "T1") (pin "T1-2") (pinfunction "L1-2_T1-2") (pintype "bidirectional"))
    )
    (net (code "105") (name "Net-(X4-ANT)") (class "Default")
      (node (ref "R52") (pin "2") (pinfunction "2_2") (pintype "passive"))
      (node (ref "R53") (pin "2") (pinfunction "2_2") (pintype "passive"))
      (node (ref "X4") (pin "ANTENNA") (pinfunction "ANT_ANTENNA") (pintype "bidirectional"))
    )
    (net (code "106") (name "OUTPUT_RELAY_CTRL") (class "Default")
      (node (ref "P2") (pin "11") (pinfunction "11_11") (pintype "passive"))
      (node (ref "R54") (pin "1") (pinfunction "1_1") (pintype "passive"))
      (node (ref "R55") (pin "2") (pinfunction "2_2") (pintype "passive"))
    )
    (net (code "107") (name "RF_AMPLIFIED_OUT_FILT") (class "Default")
      (node (ref "L5") (pin "2") (pinfunction "2_2") (pintype "passive"))
      (node (ref "R33") (pin "1") (pinfunction "1_1") (pintype "passive"))
      (node (ref "RL10") (pin "3") (pinfunction "3_3") (pintype "passive"))
      (node (ref "RL15") (pin "3") (pinfunction "3_3") (pintype "passive"))
      (node (ref "RL16") (pin "1") (pinfunction "1_1") (pintype "passive"))
      (node (ref "RL2") (pin "3") (pinfunction "3_3") (pintype "passive"))
      (node (ref "RL4") (pin "3") (pinfunction "3_3") (pintype "passive"))
      (node (ref "RL6") (pin "3") (pinfunction "3_3") (pintype "passive"))
      (node (ref "RL8") (pin "3") (pinfunction "3_3") (pintype "passive"))
    )
    (net (code "108") (name "RF_AMPLIFIED_OUT_TRANS") (class "Default")
      (node (ref "D1") (pin "A") (pinfunction "ANODE_A") (pintype "bidirectional"))
      (node (ref "L1") (pin "1") (pinfunction "1_1") (pintype "passive"))
      (node (ref "R4") (pin "2") (pinfunction "2_2") (pintype "passive"))
      (node (ref "RL1") (pin "3") (pinfunction "3_3") (pintype "passive"))
      (node (ref "RL11") (pin "1") (pinfunction "1_1") (pintype "passive"))
      (node (ref "RL3") (pin "3") (pinfunction "3_3") (pintype "passive"))
      (node (ref "RL5") (pin "3") (pinfunction "3_3") (pintype "passive"))
      (node (ref "RL7") (pin "3") (pinfunction "3_3") (pintype "passive"))
      (node (ref "RL9") (pin "3") (pinfunction "3_3") (pintype "passive"))
      (node (ref "T1") (pin "L1-2") (pinfunction "C1-2_L1-2") (pintype "bidirectional"))
      (node (ref "T1") (pin "T2-2") (pinfunction "L2-2_T2-2") (pintype "bidirectional"))
    )
    (net (code "109") (name "RF_AMPLIFIED_OUT_UNFILT") (class "Default")
      (node (ref "T1") (pin "T2-1") (pinfunction "L2-1_T2-1") (pintype "bidirectional"))
      (node (ref "X1") (pin "1") (pinfunction "1_1") (pintype "passive"))
      (node (ref "X1") (pin "2") (pinfunction "2_2") (pintype "passive"))
    )
    (net (code "110") (name "RF_OUTPUT") (class "Default")
      (node (ref "RL16") (pin "3") (pinfunction "3_3") (pintype "passive"))
      (node (ref "X3") (pin "1") (pinfunction "1_1") (pintype "passive"))
      (node (ref "X3") (pin "2") (pinfunction "2_2") (pintype "passive"))
    )
    (net (code "111") (name "RVS") (class "Default")
      (node (ref "C16") (pin "2") (pinfunction "2_2") (pintype "passive"))
      (node (ref "C17") (pin "1") (pinfunction "1_1") (pintype "passive"))
      (node (ref "D4") (pin "A") (pinfunction "ANODE_A") (pintype "bidirectional"))
      (node (ref "D8") (pin "C") (pinfunction "CATHODE_C") (pintype "bidirectional"))
      (node (ref "R10") (pin "2") (pinfunction "2_2") (pintype "passive"))
      (node (ref "R11") (pin "2") (pinfunction "2_2") (pintype "passive"))
      (node (ref "U2") (pin "3") (pinfunction "VIN_3") (pintype "input"))
    )
    (net (code "112") (name "VALVE_5V") (class "Default")
      (node (ref "C1") (pin "1") (pinfunction "1_1") (pintype "passive"))
      (node (ref "C2") (pin "1") (pinfunction "1_1") (pintype "passive"))
      (node (ref "C3") (pin "1") (pinfunction "1_1") (pintype "passive"))
      (node (ref "C4") (pin "1") (pinfunction "1_1") (pintype "passive"))
      (node (ref "C5") (pin "1") (pinfunction "1_1") (pintype "passive"))
      (node (ref "C6") (pin "1") (pinfunction "1_1") (pintype "passive"))
      (node (ref "C7") (pin "1") (pinfunction "1_1") (pintype "passive"))
      (node (ref "C8") (pin "1") (pinfunction "1_1") (pintype "passive"))
      (node (ref "D3") (pin "C") (pinfunction "CATHODE_C") (pintype "bidirectional"))
      (node (ref "D4") (pin "C") (pinfunction "CATHODE_C") (pintype "bidirectional"))
      (node (ref "P1") (pin "1") (pinfunction "1_1") (pintype "passive"))
      (node (ref "P1") (pin "2") (pinfunction "2_2") (pintype "passive"))
      (node (ref "P1") (pin "3") (pinfunction "3_3") (pintype "passive"))
      (node (ref "P1") (pin "4") (pinfunction "4_4") (pintype "passive"))
      (node (ref "P1") (pin "5") (pinfunction "5_5") (pintype "passive"))
      (node (ref "P1") (pin "6") (pinfunction "6_6") (pintype "passive"))
      (node (ref "P1") (pin "7") (pinfunction "7_7") (pintype "passive"))
      (node (ref "P1") (pin "8") (pinfunction "8_8") (pintype "passive"))
      (node (ref "U1") (pin "1") (pinfunction "VA_1") (pintype "power_in"))
      (node (ref "U2") (pin "1") (pinfunction "VA_1") (pintype "power_in"))
    )
    (net (code "113") (name "VALVE_GND") (class "Default")
      (node (ref "C1") (pin "2") (pinfunction "2_2") (pintype "passive"))
      (node (ref "C11") (pin "2") (pinfunction "2_2") (pintype "passive"))
      (node (ref "C12") (pin "2") (pinfunction "2_2") (pintype "passive"))
      (node (ref "C13") (pin "1") (pinfunction "1_1") (pintype "passive"))
      (node (ref "C14") (pin "1") (pinfunction "1_1") (pintype "passive"))
      (node (ref "C17") (pin "2") (pinfunction "2_2") (pintype "passive"))
      (node (ref "C18") (pin "2") (pinfunction "2_2") (pintype "passive"))
      (node (ref "C2") (pin "2") (pinfunction "2_2") (pintype "passive"))
      (node (ref "C3") (pin "2") (pinfunction "2_2") (pintype "passive"))
      (node (ref "C39") (pin "2") (pinfunction "2_2") (pintype "passive"))
      (node (ref "C4") (pin "2") (pinfunction "2_2") (pintype "passive"))
      (node (ref "C40") (pin "2") (pinfunction "2_2") (pintype "passive"))
      (node (ref "C41") (pin "2") (pinfunction "2_2") (pintype "passive"))
      (node (ref "C42") (pin "2") (pinfunction "2_2") (pintype "passive"))
      (node (ref "C43") (pin "2") (pinfunction "2_2") (pintype "passive"))
      (node (ref "C44") (pin "2") (pinfunction "2_2") (pintype "passive"))
      (node (ref "C45") (pin "2") (pinfunction "2_2") (pintype "passive"))
      (node (ref "C46") (pin "2") (pinfunction "2_2") (pintype "passive"))
      (node (ref "C47") (pin "2") (pinfunction "2_2") (pintype "passive"))
      (node (ref "C48") (pin "2") (pinfunction "2_2") (pintype "passive"))
      (node (ref "C5") (pin "2") (pinfunction "2_2") (pintype "passive"))
      (node (ref "C59") (pin "2") (pinfunction "2_2") (pintype "passive"))
      (node (ref "C6") (pin "2") (pinfunction "2_2") (pintype "passive"))
      (node (ref "C60") (pin "2") (pinfunction "2_2") (pintype "passive"))
      (node (ref "C61") (pin "2") (pinfunction "2_2") (pintype "passive"))
      (node (ref "C62") (pin "2") (pinfunction "2_2") (pintype "passive"))
      (node (ref "C63") (pin "2") (pinfunction "2_2") (pintype "passive"))
      (node (ref "C64") (pin "2") (pinfunction "2_2") (pintype "passive"))
      (node (ref "C65") (pin "2") (pinfunction "2_2") (pintype "passive"))
      (node (ref "C66") (pin "2") (pinfunction "2_2") (pintype "passive"))
      (node (ref "C67") (pin "2") (pinfunction "2_2") (pintype "passive"))
      (node (ref "C68") (pin "2") (pinfunction "2_2") (pintype "passive"))
      (node (ref "C7") (pin "2") (pinfunction "2_2") (pintype "passive"))
      (node (ref "C8") (pin "2") (pinfunction "2_2") (pintype "passive"))
      (node (ref "D7") (pin "A") (pinfunction "ANODE_A") (pintype "bidirectional"))
      (node (ref "D8") (pin "A") (pinfunction "ANODE_A") (pintype "bidirectional"))
      (node (ref "P1") (pin "14") (pinfunction "14_14") (pintype "passive"))
      (node (ref "P1") (pin "15") (pinfunction "15_15") (pintype "passive"))
      (node (ref "P1") (pin "16") (pinfunction "16_16") (pintype "passive"))
      (node (ref "P1") (pin "17") (pinfunction "17_17") (pintype "passive"))
      (node (ref "P1") (pin "18") (pinfunction "18_18") (pintype "passive"))
      (node (ref "P1") (pin "19") (pinfunction "19_19") (pintype "passive"))
      (node (ref "P1") (pin "20") (pinfunction "20_20") (pintype "passive"))
      (node (ref "R11") (pin "1") (pinfunction "1_1") (pintype "passive"))
      (node (ref "R12") (pin "1") (pinfunction "1_1") (pintype "passive"))
      (node (ref "R5") (pin "1") (pinfunction "1_1") (pintype "passive"))
      (node (ref "R53") (pin "1") (pinfunction "1_1") (pintype "passive"))
      (node (ref "R6") (pin "2") (pinfunction "2_2") (pintype "passive"))
      (node (ref "T1") (pin "L1-1") (pinfunction "C1-1_L1-1") (pintype "bidirectional"))
      (node (ref "T1") (pin "L2-1") (pinfunction "C2-1_L2-1") (pintype "bidirectional"))
      (node (ref "U1") (pin "2") (pinfunction "GND_2") (pintype "power_in"))
      (node (ref "U2") (pin "2") (pinfunction "GND_2") (pintype "power_in"))
      (node (ref "X4") (pin "GND1") (pinfunction "GND1_GND1") (pintype "power_in"))
      (node (ref "X4") (pin "GND2") (pinfunction "GND2_GND2") (pintype "power_in"))
      (node (ref "X4") (pin "GND3") (pinfunction "GND3_GND3") (pintype "power_in"))
      (node (ref "X4") (pin "GND4") (pinfunction "GND4_GND4") (pintype "power_in"))
    )
    (net (code "114") (name "V_MISO") (class "Default")
      (node (ref "P1") (pin "11") (pinfunction "11_11") (pintype "passive"))
      (node (ref "U1") (pin "5") (pinfunction "SDATA_5") (pintype "output"))
      (node (ref "U2") (pin "5") (pinfunction "SDATA_5") (pintype "output"))
    )
    (net (code "115") (name "V_MOSI") (class "Default")
      (node (ref "P1") (pin "13") (pinfunction "13_13") (pintype "passive"))
    )
    (net (code "116") (name "V_SCLK") (class "Default")
      (node (ref "P1") (pin "12") (pinfunction "12_12") (pintype "passive"))
      (node (ref "U1") (pin "4") (pinfunction "SCLK_4") (pintype "input"))
      (node (ref "U2") (pin "4") (pinfunction "SCLK_4") (pintype "input"))
    )
    (net (code "117") (name "unconnected-(RL1-Pad4)") (class "Default")
      (node (ref "RL1") (pin "4") (pinfunction "4_4") (pintype "passive"))
    )
    (net (code "118") (name "unconnected-(RL2-Pad4)") (class "Default")
      (node (ref "RL2") (pin "4") (pinfunction "4_4") (pintype "passive"))
    )
    (net (code "119") (name "unconnected-(RL3-Pad4)") (class "Default")
      (node (ref "RL3") (pin "4") (pinfunction "4_4") (pintype "passive"))
    )
    (net (code "120") (name "unconnected-(RL4-Pad4)") (class "Default")
      (node (ref "RL4") (pin "4") (pinfunction "4_4") (pintype "passive"))
    )
    (net (code "121") (name "unconnected-(RL5-Pad4)") (class "Default")
      (node (ref "RL5") (pin "4") (pinfunction "4_4") (pintype "passive"))
    )
    (net (code "122") (name "unconnected-(RL6-Pad4)") (class "Default")
      (node (ref "RL6") (pin "4") (pinfunction "4_4") (pintype "passive"))
    )
    (net (code "123") (name "unconnected-(RL7-Pad4)") (class "Default")
      (node (ref "RL7") (pin "4") (pinfunction "4_4") (pintype "passive"))
    )
    (net (code "124") (name "unconnected-(RL8-Pad4)") (class "Default")
      (node (ref "RL8") (pin "4") (pinfunction "4_4") (pintype "passive"))
    )
    (net (code "125") (name "unconnected-(RL9-Pad4)") (class "Default")
      (node (ref "RL9") (pin "4") (pinfunction "4_4") (pintype "passive"))
    )
    (net (code "126") (name "unconnected-(RL10-Pad4)") (class "Default")
      (node (ref "RL10") (pin "4") (pinfunction "4_4") (pintype "passive"))
    )
    (net (code "127") (name "unconnected-(RL11-Pad4)") (class "Default")
      (node (ref "RL11") (pin "4") (pinfunction "4_4") (pintype "passive"))
    )
    (net (code "128") (name "unconnected-(RL12-Pad4)") (class "Default")
      (node (ref "RL12") (pin "4") (pinfunction "4_4") (pintype "passive"))
    )
    (net (code "129") (name "unconnected-(RL13-Pad4)") (class "Default")
      (node (ref "RL13") (pin "4") (pinfunction "4_4") (pintype "passive"))
    )
    (net (code "130") (name "unconnected-(RL14-Pad4)") (class "Default")
      (node (ref "RL14") (pin "4") (pinfunction "4_4") (pintype "passive"))
    )
    (net (code "131") (name "unconnected-(RL15-Pad4)") (class "Default")
      (node (ref "RL15") (pin "4") (pinfunction "4_4") (pintype "passive"))
    )
    (net (code "132") (name "unconnected-(RL16-Pad4)") (class "Default")
      (node (ref "RL16") (pin "4") (pinfunction "4_4") (pintype "passive"))
    )
    (net (code "133") (name "~{V_OUT_FWD_SS}") (class "Default")
      (node (ref "P1") (pin "9") (pinfunction "9_9") (pintype "passive"))
      (node (ref "U1") (pin "6") (pinfunction "~{CS}_6") (pintype "passive"))
    )
    (net (code "134") (name "~{V_OUT_RVS_SS}") (class "Default")
      (node (ref "P1") (pin "10") (pinfunction "10_10") (pintype "passive"))
      (node (ref "U2") (pin "6") (pinfunction "~{CS}_6") (pintype "passive"))
    )
  )
)
